# controller.net
KiCad netlist of a schematic drawn in EAGLE
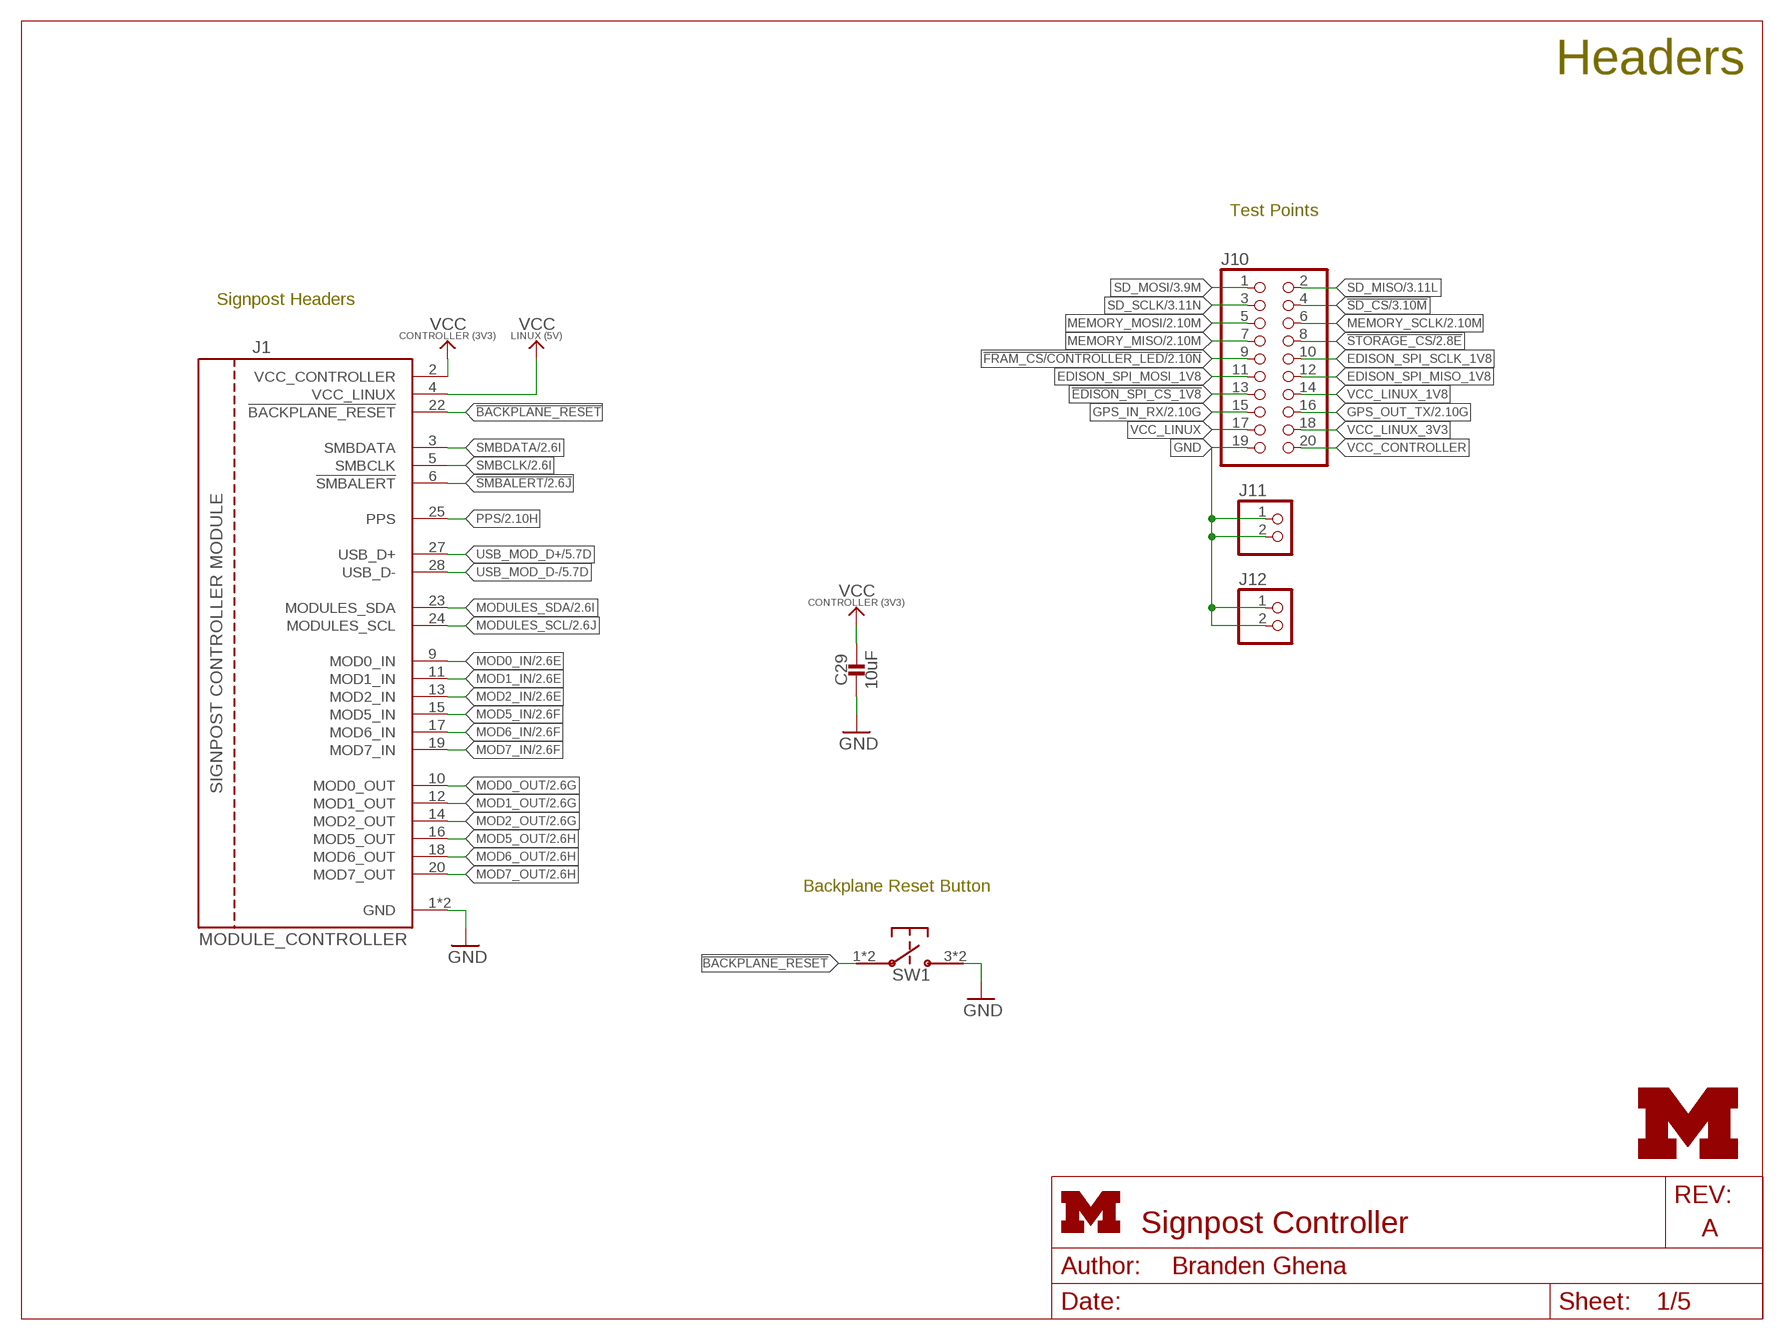
[diagram p0: schematic, sheet 1]
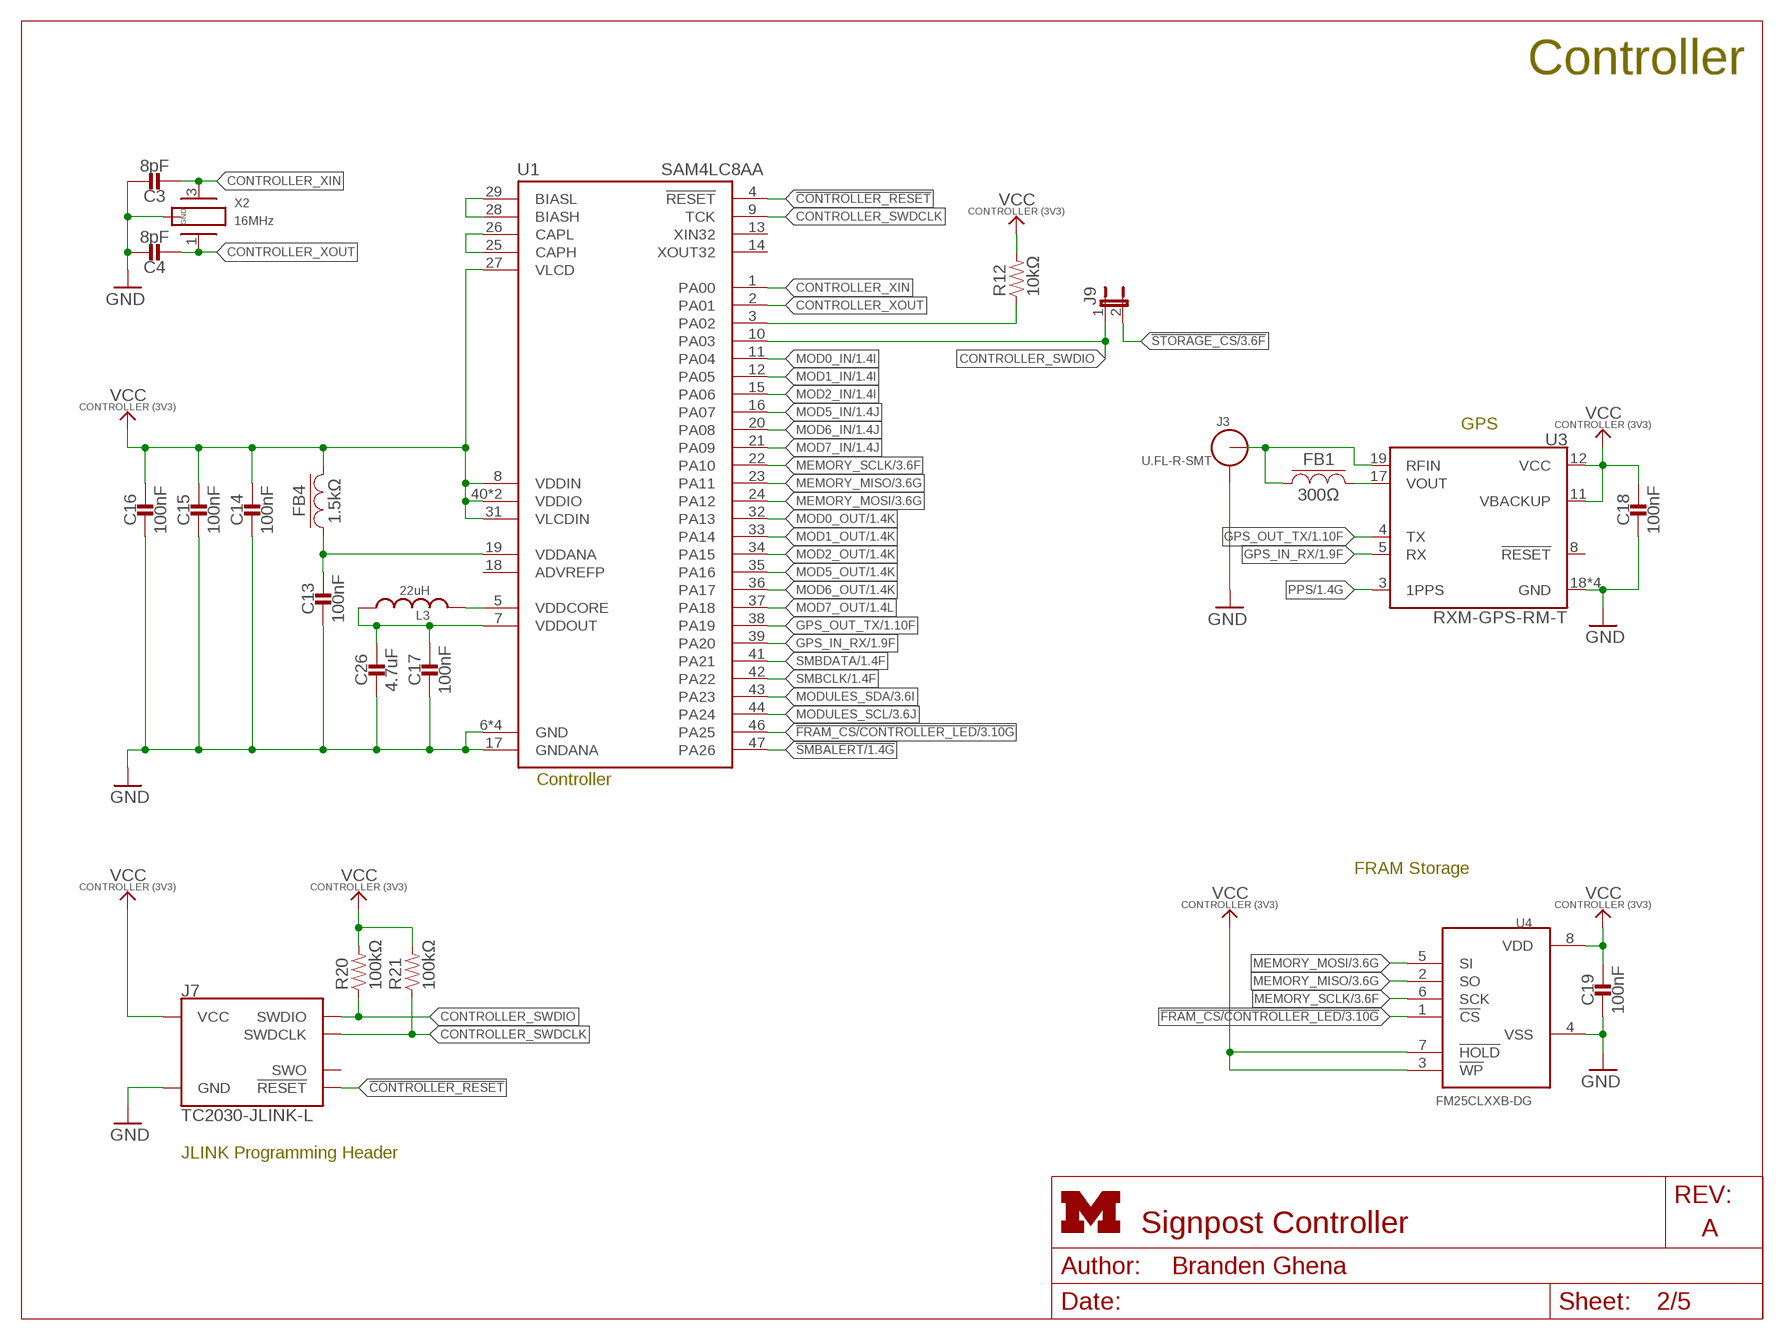
[diagram p1: schematic, sheet 2]
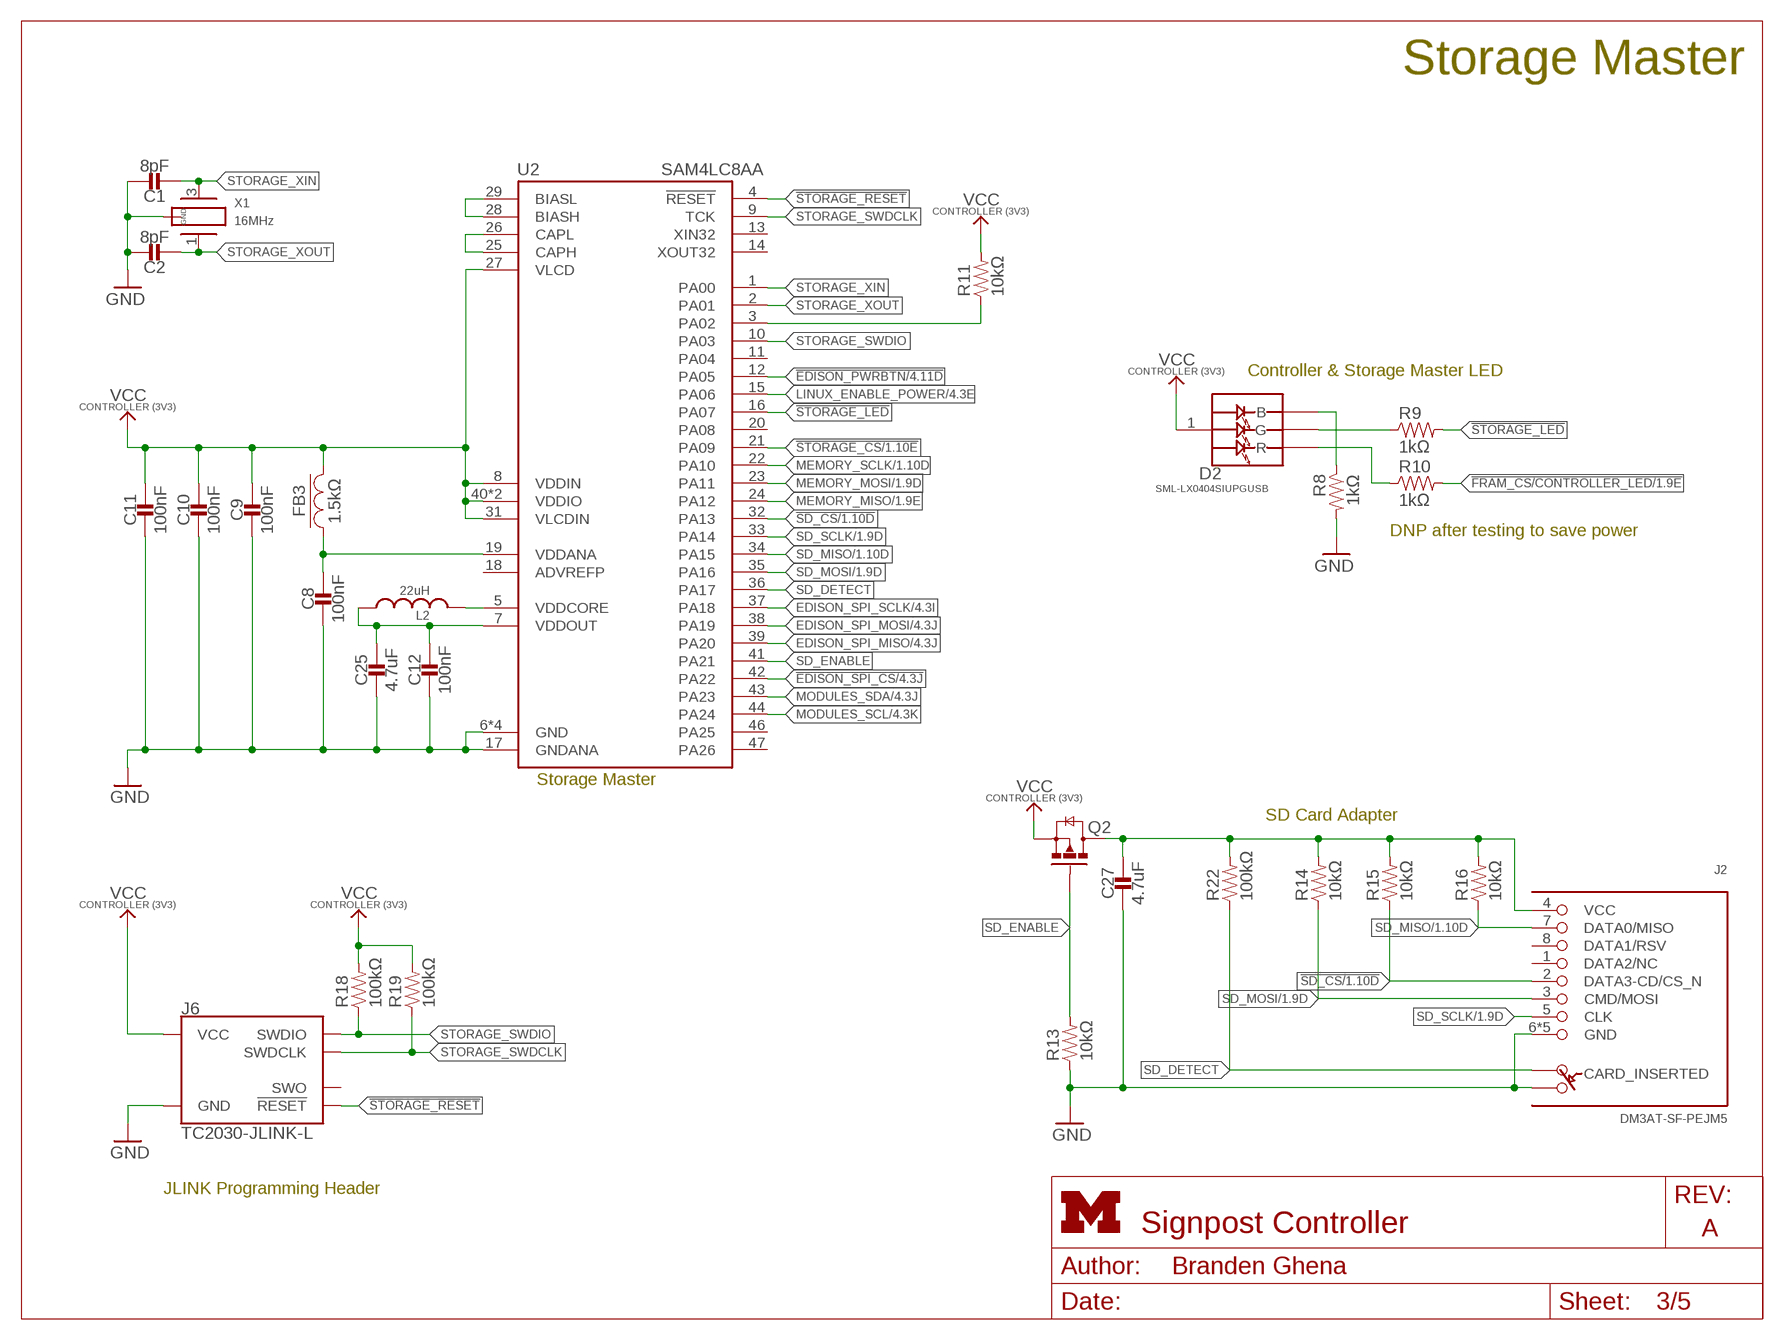
[diagram p2: schematic, sheet 3]
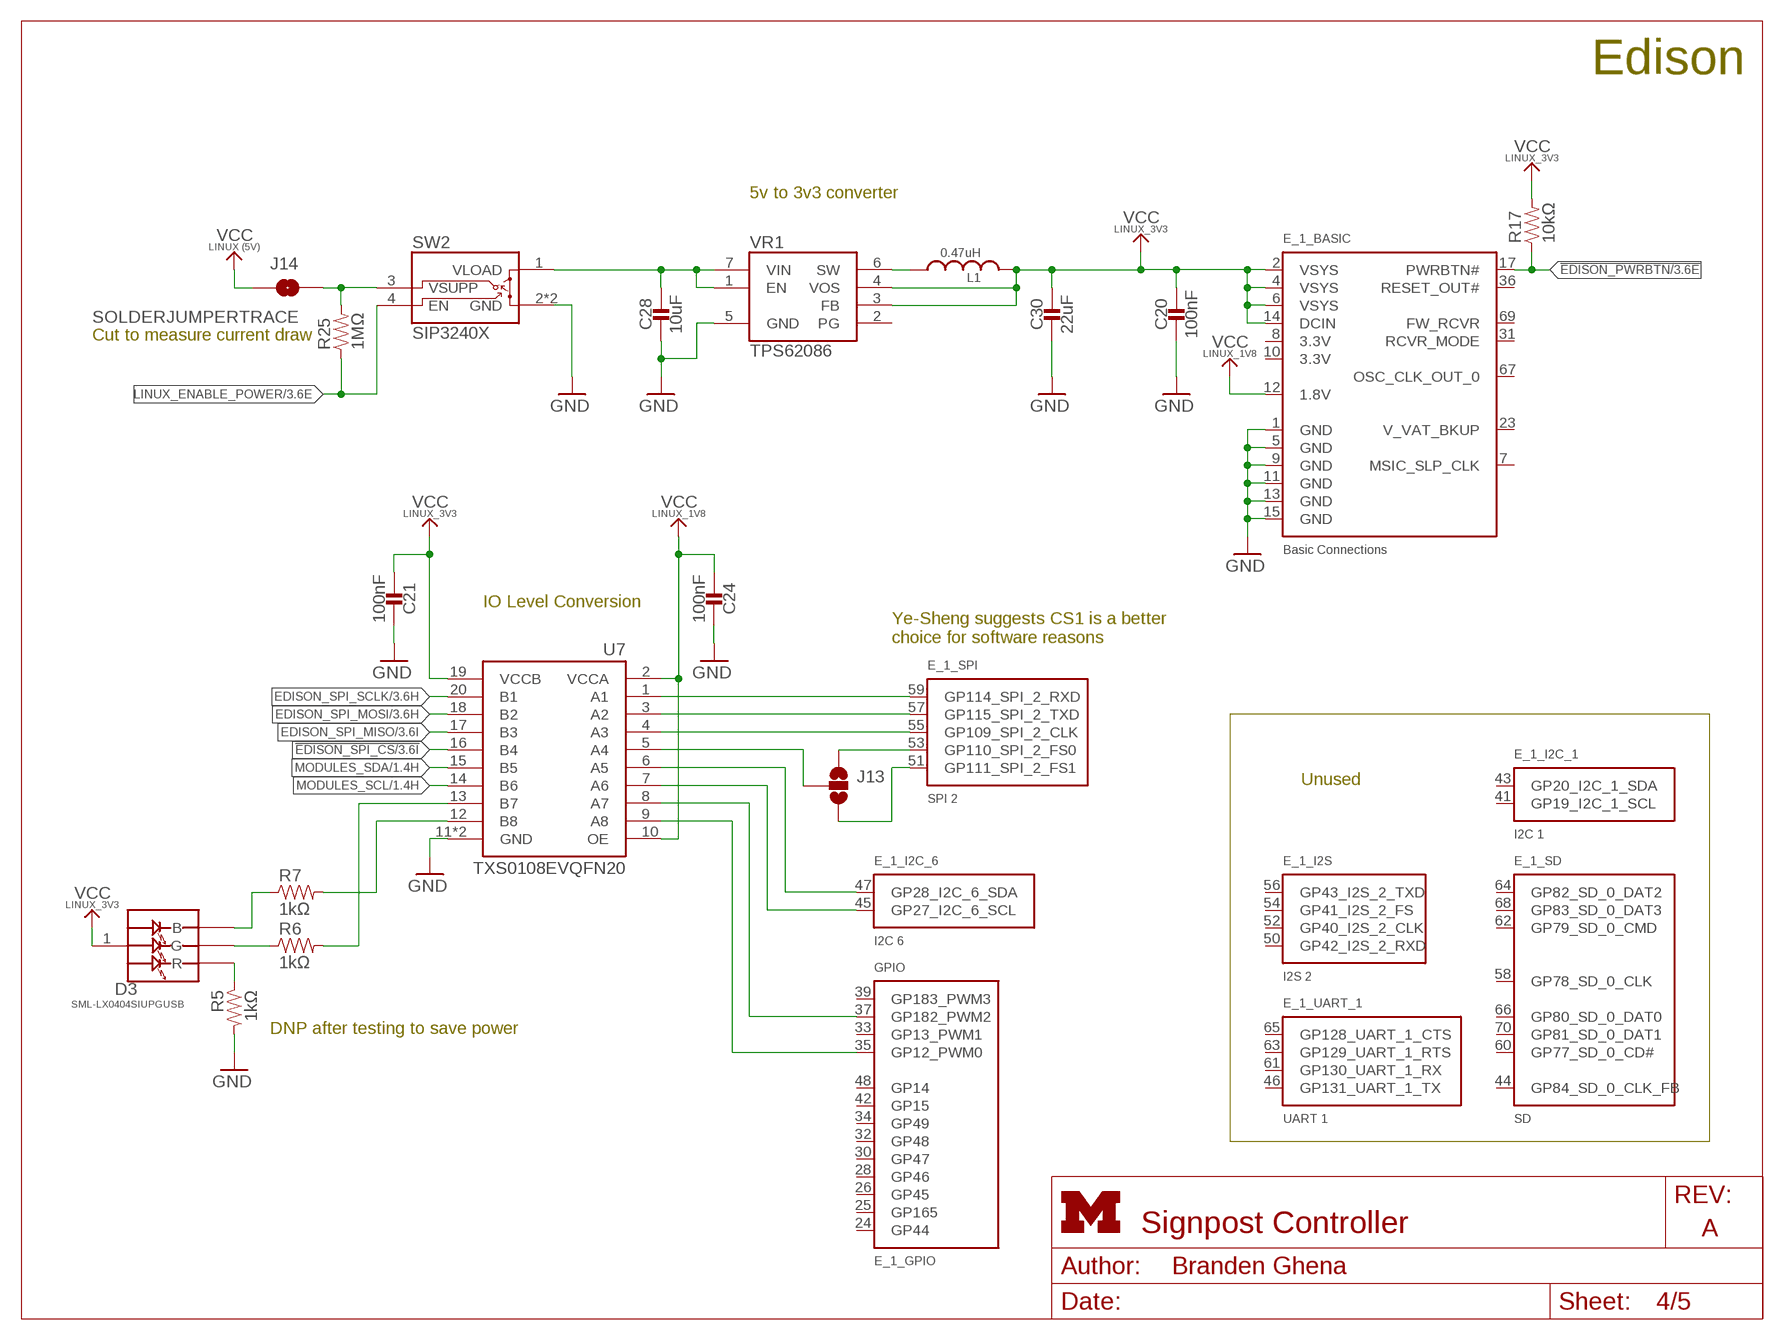
[diagram p3: schematic, sheet 4]
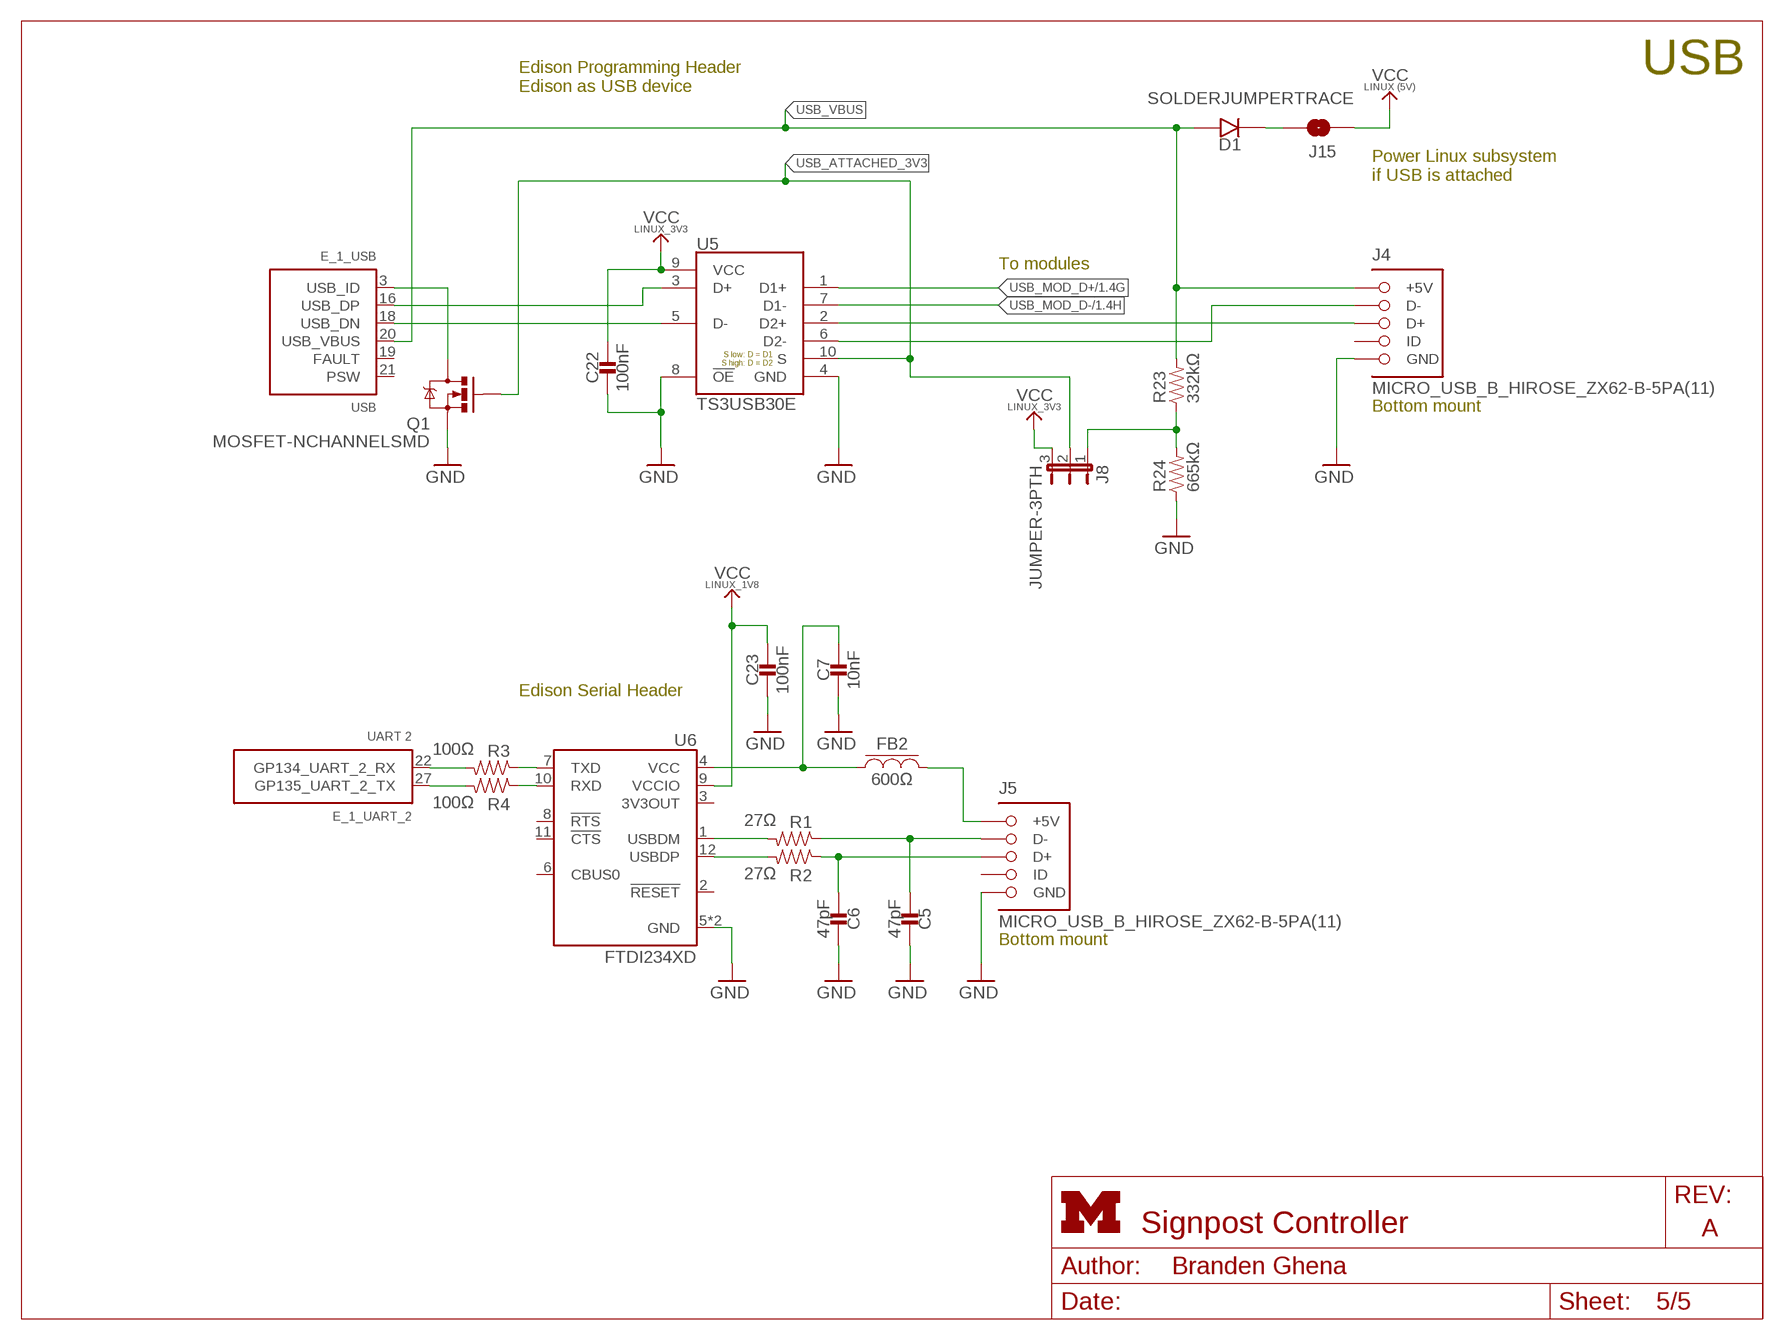
[diagram p4: schematic, sheet 5]

(export (version "E")
  (design (tool "Eeschema 10.0.6"))
  (components
    (comp (ref "C5")
      (value "47pF")
      (footprint "eagle-import:0402_CAP")
      (libsource (lib "eagle-import") (part "CAPACITOR0402_CAP"))
    )
    (comp (ref "C6")
      (value "47pF")
      (footprint "eagle-import:0402_CAP")
      (libsource (lib "eagle-import") (part "CAPACITOR0402_CAP"))
    )
    (comp (ref "C7")
      (value "10nF")
      (footprint "eagle-import:0402_CAP")
      (libsource (lib "eagle-import") (part "CAPACITOR0402_CAP"))
    )
    (comp (ref "C22")
      (value "100nF")
      (footprint "eagle-import:0402_CAP")
      (libsource (lib "eagle-import") (part "CAPACITOR0402_CAP"))
    )
    (comp (ref "C23")
      (value "100nF")
      (footprint "eagle-import:0402_CAP")
      (libsource (lib "eagle-import") (part "CAPACITOR0402_CAP"))
    )
    (comp (ref "D1")
      (value "DIODE")
      (footprint "eagle-import:0402_DIODE")
      (libsource (lib "eagle-import") (part "DIODE"))
    )
    (comp (ref "E_1")
      (value "EDISON_CONNECTOR_SEGMENTED")
      (footprint "eagle-import:EDISON_DAUGHTER")
      (fields (field (name "AMAZON") "B00PTVSS4A") (field (name "MOUSER") "798-DF40HC3070DS4V51"))
      (libsource (lib "eagle-import") (part "EDISON_CONNECTOR_SEGMENTED"))
    )
    (comp (ref "FB2")
      (value "600Ω")
      (footprint "eagle-import:0805_CAP")
      (libsource (lib "eagle-import") (part "FERRITE_BEAD0805"))
    )
    (comp (ref "J4")
      (value "MICRO_USB_B_HIROSE_ZX62-B-5PA(11)")
      (footprint "eagle-import:USB_MICRO_B-HIROSE-ZX62-B-5PA(11)")
      (libsource (lib "eagle-import") (part "MICRO_USB_B_HIROSE_ZX62-B-5PA(11)"))
    )
    (comp (ref "J5")
      (value "MICRO_USB_B_HIROSE_ZX62-B-5PA(11)")
      (footprint "eagle-import:USB_MICRO_B-HIROSE-ZX62-B-5PA(11)")
      (libsource (lib "eagle-import") (part "MICRO_USB_B_HIROSE_ZX62-B-5PA(11)"))
    )
    (comp (ref "J8")
      (value "JUMPER-3PTH")
      (footprint "eagle-import:1X03")
      (libsource (lib "eagle-import") (part "JUMPER-3PTH"))
    )
    (comp (ref "J15")
      (value "SOLDERJUMPERTRACE")
      (footprint "eagle-import:SJ_2S-TRACE")
      (libsource (lib "eagle-import") (part "SOLDERJUMPERTRACE"))
    )
    (comp (ref "Q1")
      (value "MOSFET-NCHANNELSMD")
      (footprint "eagle-import:SOT23-3")
      (libsource (lib "eagle-import") (part "MOSFET-NCHANNELSMD"))
    )
    (comp (ref "R1")
      (value "27Ω")
      (footprint "eagle-import:0402_RES")
      (libsource (lib "eagle-import") (part "RESISTOR0402_RES"))
    )
    (comp (ref "R2")
      (value "27Ω")
      (footprint "eagle-import:0402_RES")
      (libsource (lib "eagle-import") (part "RESISTOR0402_RES"))
    )
    (comp (ref "R3")
      (value "100Ω")
      (footprint "eagle-import:0402_RES")
      (libsource (lib "eagle-import") (part "RESISTOR0402_RES"))
    )
    (comp (ref "R4")
      (value "100Ω")
      (footprint "eagle-import:0402_RES")
      (libsource (lib "eagle-import") (part "RESISTOR0402_RES"))
    )
    (comp (ref "R23")
      (value "332kΩ")
      (footprint "eagle-import:0402_RES")
      (libsource (lib "eagle-import") (part "RESISTOR0402_RES"))
    )
    (comp (ref "R24")
      (value "665kΩ")
      (footprint "eagle-import:0402_RES")
      (libsource (lib "eagle-import") (part "RESISTOR0402_RES"))
    )
    (comp (ref "U5")
      (value "TS3USB30E")
      (footprint "eagle-import:UQFN-10")
      (libsource (lib "eagle-import") (part "TS3USB30E"))
    )
    (comp (ref "U6")
      (value "FTDI234XD")
      (footprint "eagle-import:DFN-12_3MM")
      (libsource (lib "eagle-import") (part "FTDI234XD"))
    )
    (comp (ref "C29")
      (value "10uF")
      (footprint "eagle-import:0402_CAP")
      (libsource (lib "eagle-import") (part "CAPACITOR0402_CAP"))
    )
    (comp (ref "J1")
      (value "MODULE_CONTROLLER")
      (footprint "eagle-import:MODULE_CONTROLLER")
      (libsource (lib "eagle-import") (part "MODULE_CONTROLLER"))
    )
    (comp (ref "J10")
      (value "PINHD-2X10")
      (footprint "eagle-import:2X10")
      (libsource (lib "eagle-import") (part "PINHD-2X10"))
    )
    (comp (ref "J11")
      (value "PINHD-1X2")
      (footprint "eagle-import:1X02")
      (libsource (lib "eagle-import") (part "PINHD-1X2"))
    )
    (comp (ref "J12")
      (value "PINHD-1X2")
      (footprint "eagle-import:1X02")
      (libsource (lib "eagle-import") (part "PINHD-1X2"))
    )
    (comp (ref "LOGO1")
      (value "UMICH_SOLID_MEDIUM")
      (footprint "eagle-import:UMICH_SOLID_200MIL")
      (libsource (lib "eagle-import") (part "UMICH_SOLID_MEDIUM"))
    )
    (comp (ref "SW1")
      (value "PTS810SJ")
      (footprint "eagle-import:PTS810SJ")
      (libsource (lib "eagle-import") (part "PTS810SJ"))
    )
    (comp (ref "C3")
      (value "8pF")
      (footprint "eagle-import:0402_CAP")
      (libsource (lib "eagle-import") (part "CAPACITOR0402_CAP"))
    )
    (comp (ref "C4")
      (value "8pF")
      (footprint "eagle-import:0402_CAP")
      (libsource (lib "eagle-import") (part "CAPACITOR0402_CAP"))
    )
    (comp (ref "C13")
      (value "100nF")
      (footprint "eagle-import:0402_CAP")
      (libsource (lib "eagle-import") (part "CAPACITOR0402_CAP"))
    )
    (comp (ref "C14")
      (value "100nF")
      (footprint "eagle-import:0402_CAP")
      (libsource (lib "eagle-import") (part "CAPACITOR0402_CAP"))
    )
    (comp (ref "C15")
      (value "100nF")
      (footprint "eagle-import:0402_CAP")
      (libsource (lib "eagle-import") (part "CAPACITOR0402_CAP"))
    )
    (comp (ref "C16")
      (value "100nF")
      (footprint "eagle-import:0402_CAP")
      (libsource (lib "eagle-import") (part "CAPACITOR0402_CAP"))
    )
    (comp (ref "C17")
      (value "100nF")
      (footprint "eagle-import:0402_CAP")
      (libsource (lib "eagle-import") (part "CAPACITOR0402_CAP"))
    )
    (comp (ref "C18")
      (value "100nF")
      (footprint "eagle-import:0402_CAP")
      (libsource (lib "eagle-import") (part "CAPACITOR0402_CAP"))
    )
    (comp (ref "C19")
      (value "100nF")
      (footprint "eagle-import:0402_CAP")
      (libsource (lib "eagle-import") (part "CAPACITOR0402_CAP"))
    )
    (comp (ref "C26")
      (value "4.7uF")
      (footprint "eagle-import:0402_CAP")
      (libsource (lib "eagle-import") (part "CAPACITOR0402_CAP"))
    )
    (comp (ref "FB1")
      (value "300Ω")
      (footprint "eagle-import:0402_CAP")
      (libsource (lib "eagle-import") (part "FERRITE_BEAD0402"))
    )
    (comp (ref "FB4")
      (value "1.5kΩ")
      (footprint "eagle-import:0402_CAP")
      (libsource (lib "eagle-import") (part "FERRITE_BEAD0402"))
    )
    (comp (ref "J3")
      (value "U.FL-R-SMT")
      (footprint "eagle-import:U.FL_SMT")
      (libsource (lib "eagle-import") (part "U.FL-R-SMT"))
    )
    (comp (ref "J7")
      (value "TC2030-JLINK-L")
      (footprint "eagle-import:TC2030-IDC")
      (libsource (lib "eagle-import") (part "TC2030-JLINK-L"))
    )
    (comp (ref "J9")
      (value "JUMPER-2PTH")
      (footprint "eagle-import:1X02")
      (libsource (lib "eagle-import") (part "JUMPER-2PTH"))
    )
    (comp (ref "L3")
      (value "22uH")
      (footprint "eagle-import:1212")
      (libsource (lib "eagle-import") (part "LHQ3NP"))
    )
    (comp (ref "R12")
      (value "10kΩ")
      (footprint "eagle-import:0402_RES")
      (libsource (lib "eagle-import") (part "RESISTOR0402_RES"))
    )
    (comp (ref "R20")
      (value "100kΩ")
      (footprint "eagle-import:0402_RES")
      (libsource (lib "eagle-import") (part "RESISTOR0402_RES"))
    )
    (comp (ref "R21")
      (value "100kΩ")
      (footprint "eagle-import:0402_RES")
      (libsource (lib "eagle-import") (part "RESISTOR0402_RES"))
    )
    (comp (ref "U1")
      (value "SAM4LC8AA")
      (footprint "eagle-import:QFN-48-7MM")
      (libsource (lib "eagle-import") (part "SAM4LC8AA"))
    )
    (comp (ref "U3")
      (value "RXM-GPS-RM-T")
      (footprint "eagle-import:RXM-GPS-RM-T")
      (libsource (lib "eagle-import") (part "RXM-GPS-RM-T"))
    )
    (comp (ref "U4")
      (value "FM25CLXXB-DG")
      (footprint "eagle-import:TDFN-8")
      (libsource (lib "eagle-import") (part "FM25CLXXB-DG"))
    )
    (comp (ref "X2")
      (value "16MHz")
      (footprint "eagle-import:FHXXX")
      (libsource (lib "eagle-import") (part "FH1600015"))
    )
    (comp (ref "C20")
      (value "100nF")
      (footprint "eagle-import:0402_CAP")
      (libsource (lib "eagle-import") (part "CAPACITOR0402_CAP"))
    )
    (comp (ref "C21")
      (value "100nF")
      (footprint "eagle-import:0402_CAP")
      (libsource (lib "eagle-import") (part "CAPACITOR0402_CAP"))
    )
    (comp (ref "C24")
      (value "100nF")
      (footprint "eagle-import:0402_CAP")
      (libsource (lib "eagle-import") (part "CAPACITOR0402_CAP"))
    )
    (comp (ref "C28")
      (value "10uF")
      (footprint "eagle-import:0805_CAP")
      (libsource (lib "eagle-import") (part "CAPACITOR0805_CAP"))
    )
    (comp (ref "C30")
      (value "22uF")
      (footprint "eagle-import:0805_CAP")
      (libsource (lib "eagle-import") (part "CAPACITOR0805_CAP"))
    )
    (comp (ref "D3")
      (value "SML-LX0404SIUPGUSB")
      (footprint "eagle-import:1MM_SQ_4PAD")
      (libsource (lib "eagle-import") (part "SML-LX0404SIUPGUSB"))
    )
    (comp (ref "J13")
      (value "SOLDERJUMPER_2WAYPASTE2&3")
      (footprint "eagle-import:SJ_3_PASTE2&3")
      (libsource (lib "eagle-import") (part "SOLDERJUMPER_2WAYPASTE2&3"))
    )
    (comp (ref "J14")
      (value "SOLDERJUMPERTRACE")
      (footprint "eagle-import:SJ_2S-TRACE")
      (libsource (lib "eagle-import") (part "SOLDERJUMPERTRACE"))
    )
    (comp (ref "L1")
      (value "0.47uH")
      (footprint "eagle-import:DFE322512C")
      (libsource (lib "eagle-import") (part "INDUCTORDFE322512C"))
    )
    (comp (ref "R5")
      (value "1kΩ")
      (footprint "eagle-import:0402_RES")
      (libsource (lib "eagle-import") (part "RESISTOR0402_RES"))
    )
    (comp (ref "R6")
      (value "1kΩ")
      (footprint "eagle-import:0402_RES")
      (libsource (lib "eagle-import") (part "RESISTOR0402_RES"))
    )
    (comp (ref "R7")
      (value "1kΩ")
      (footprint "eagle-import:0402_RES")
      (libsource (lib "eagle-import") (part "RESISTOR0402_RES"))
    )
    (comp (ref "R17")
      (value "10kΩ")
      (footprint "eagle-import:0402_RES")
      (libsource (lib "eagle-import") (part "RESISTOR0402_RES"))
    )
    (comp (ref "R25")
      (value "1MΩ")
      (footprint "eagle-import:0402_RES")
      (libsource (lib "eagle-import") (part "RESISTOR0402_RES"))
    )
    (comp (ref "SW2")
      (value "SIP3240X")
      (footprint "eagle-import:TDFN4")
      (libsource (lib "eagle-import") (part "SIP3240X"))
    )
    (comp (ref "U7")
      (value "TXS0108EVQFN20")
      (footprint "eagle-import:R-PVQFN-N20")
      (libsource (lib "eagle-import") (part "TXS0108EVQFN20"))
    )
    (comp (ref "VR1")
      (value "TPS62086")
      (footprint "eagle-import:RLT0007A")
      (libsource (lib "eagle-import") (part "TPS62086"))
    )
    (comp (ref "C1")
      (value "8pF")
      (footprint "eagle-import:0402_CAP")
      (libsource (lib "eagle-import") (part "CAPACITOR0402_CAP"))
    )
    (comp (ref "C2")
      (value "8pF")
      (footprint "eagle-import:0402_CAP")
      (libsource (lib "eagle-import") (part "CAPACITOR0402_CAP"))
    )
    (comp (ref "C8")
      (value "100nF")
      (footprint "eagle-import:0402_CAP")
      (libsource (lib "eagle-import") (part "CAPACITOR0402_CAP"))
    )
    (comp (ref "C9")
      (value "100nF")
      (footprint "eagle-import:0402_CAP")
      (libsource (lib "eagle-import") (part "CAPACITOR0402_CAP"))
    )
    (comp (ref "C10")
      (value "100nF")
      (footprint "eagle-import:0402_CAP")
      (libsource (lib "eagle-import") (part "CAPACITOR0402_CAP"))
    )
    (comp (ref "C11")
      (value "100nF")
      (footprint "eagle-import:0402_CAP")
      (libsource (lib "eagle-import") (part "CAPACITOR0402_CAP"))
    )
    (comp (ref "C12")
      (value "100nF")
      (footprint "eagle-import:0402_CAP")
      (libsource (lib "eagle-import") (part "CAPACITOR0402_CAP"))
    )
    (comp (ref "C25")
      (value "4.7uF")
      (footprint "eagle-import:0402_CAP")
      (libsource (lib "eagle-import") (part "CAPACITOR0402_CAP"))
    )
    (comp (ref "C27")
      (value "4.7uF")
      (footprint "eagle-import:0402_CAP")
      (libsource (lib "eagle-import") (part "CAPACITOR0402_CAP"))
    )
    (comp (ref "D2")
      (value "SML-LX0404SIUPGUSB")
      (footprint "eagle-import:1MM_SQ_4PAD")
      (libsource (lib "eagle-import") (part "SML-LX0404SIUPGUSB"))
    )
    (comp (ref "FB3")
      (value "1.5kΩ")
      (footprint "eagle-import:0402_CAP")
      (libsource (lib "eagle-import") (part "FERRITE_BEAD0402"))
    )
    (comp (ref "J2")
      (value "DM3AT-SF-PEJM5")
      (footprint "eagle-import:DM3AT-SF-PEJM5")
      (libsource (lib "eagle-import") (part "DM3AT-SF-PEJM5"))
    )
    (comp (ref "J6")
      (value "TC2030-JLINK-L")
      (footprint "eagle-import:TC2030-IDC")
      (libsource (lib "eagle-import") (part "TC2030-JLINK-L"))
    )
    (comp (ref "L2")
      (value "22uH")
      (footprint "eagle-import:1212")
      (libsource (lib "eagle-import") (part "LHQ3NP"))
    )
    (comp (ref "Q2")
      (value "NX3008PBK")
      (footprint "eagle-import:SOT23-3")
      (libsource (lib "eagle-import") (part "NX3008PBK"))
    )
    (comp (ref "R8")
      (value "1kΩ")
      (footprint "eagle-import:0402_RES")
      (libsource (lib "eagle-import") (part "RESISTOR0402_RES"))
    )
    (comp (ref "R9")
      (value "1kΩ")
      (footprint "eagle-import:0402_RES")
      (libsource (lib "eagle-import") (part "RESISTOR0402_RES"))
    )
    (comp (ref "R10")
      (value "1kΩ")
      (footprint "eagle-import:0402_RES")
      (libsource (lib "eagle-import") (part "RESISTOR0402_RES"))
    )
    (comp (ref "R11")
      (value "10kΩ")
      (footprint "eagle-import:0402_RES")
      (libsource (lib "eagle-import") (part "RESISTOR0402_RES"))
    )
    (comp (ref "R13")
      (value "10kΩ")
      (footprint "eagle-import:0402_RES")
      (libsource (lib "eagle-import") (part "RESISTOR0402_RES"))
    )
    (comp (ref "R14")
      (value "10kΩ")
      (footprint "eagle-import:0402_RES")
      (libsource (lib "eagle-import") (part "RESISTOR0402_RES"))
    )
    (comp (ref "R15")
      (value "10kΩ")
      (footprint "eagle-import:0402_RES")
      (libsource (lib "eagle-import") (part "RESISTOR0402_RES"))
    )
    (comp (ref "R16")
      (value "10kΩ")
      (footprint "eagle-import:0402_RES")
      (libsource (lib "eagle-import") (part "RESISTOR0402_RES"))
    )
    (comp (ref "R18")
      (value "100kΩ")
      (footprint "eagle-import:0402_RES")
      (libsource (lib "eagle-import") (part "RESISTOR0402_RES"))
    )
    (comp (ref "R19")
      (value "100kΩ")
      (footprint "eagle-import:0402_RES")
      (libsource (lib "eagle-import") (part "RESISTOR0402_RES"))
    )
    (comp (ref "R22")
      (value "100kΩ")
      (footprint "eagle-import:0402_RES")
      (libsource (lib "eagle-import") (part "RESISTOR0402_RES"))
    )
    (comp (ref "U2")
      (value "SAM4LC8AA")
      (footprint "eagle-import:QFN-48-7MM")
      (libsource (lib "eagle-import") (part "SAM4LC8AA"))
    )
    (comp (ref "X1")
      (value "16MHz")
      (footprint "eagle-import:FHXXX")
      (libsource (lib "eagle-import") (part "FH1600015"))
    )
  )
  (nets
    (net (code "1") (name "CONTROLLER_SWDCLK") (class "Default")
      (node (ref "J7") (pin "4") (pinfunction "SWDCLK_4") (pintype "bidirectional"))
      (node (ref "R21") (pin "1") (pinfunction "1_1") (pintype "passive"))
      (node (ref "U1") (pin "9") (pinfunction "TCK_9") (pintype "bidirectional"))
    )
    (net (code "2") (name "CONTROLLER_SWDIO") (class "Default")
      (node (ref "J7") (pin "2") (pinfunction "SWDIO_2") (pintype "bidirectional"))
      (node (ref "J9") (pin "1") (pinfunction "1_1") (pintype "passive"))
      (node (ref "R20") (pin "1") (pinfunction "1_1") (pintype "passive"))
      (node (ref "U1") (pin "10") (pinfunction "PA03_10") (pintype "bidirectional"))
    )
    (net (code "3") (name "CONTROLLER_XIN") (class "Default")
      (node (ref "C3") (pin "1") (pinfunction "1_1") (pintype "bidirectional"))
      (node (ref "U1") (pin "1") (pinfunction "PA00_1") (pintype "bidirectional"))
      (node (ref "X2") (pin "3") (pinfunction "2_3") (pintype "bidirectional"))
    )
    (net (code "4") (name "CONTROLLER_XOUT") (class "Default")
      (node (ref "C4") (pin "1") (pinfunction "1_1") (pintype "bidirectional"))
      (node (ref "U1") (pin "2") (pinfunction "PA01_2") (pintype "bidirectional"))
      (node (ref "X2") (pin "1") (pinfunction "1_1") (pintype "bidirectional"))
    )
    (net (code "5") (name "EDISON_SPI_MISO") (class "Default")
      (node (ref "U2") (pin "39") (pinfunction "PA20_39") (pintype "bidirectional"))
      (node (ref "U7") (pin "17") (pinfunction "B3_17") (pintype "bidirectional"))
    )
    (net (code "6") (name "EDISON_SPI_MISO_1V8") (class "Default")
      (node (ref "E_1") (pin "55") (pinfunction "GP109_SPI_2_CLK_55") (pintype "bidirectional"))
      (node (ref "J10") (pin "12") (pinfunction "12_12") (pintype "passive"))
      (node (ref "U7") (pin "4") (pinfunction "A3_4") (pintype "bidirectional"))
    )
    (net (code "7") (name "EDISON_SPI_MOSI") (class "Default")
      (node (ref "U2") (pin "38") (pinfunction "PA19_38") (pintype "bidirectional"))
      (node (ref "U7") (pin "18") (pinfunction "B2_18") (pintype "bidirectional"))
    )
    (net (code "8") (name "EDISON_SPI_MOSI_1V8") (class "Default")
      (node (ref "E_1") (pin "57") (pinfunction "GP115_SPI_2_TXD_57") (pintype "bidirectional"))
      (node (ref "J10") (pin "11") (pinfunction "11_11") (pintype "passive"))
      (node (ref "U7") (pin "3") (pinfunction "A2_3") (pintype "bidirectional"))
    )
    (net (code "9") (name "EDISON_SPI_SCLK") (class "Default")
      (node (ref "U2") (pin "37") (pinfunction "PA18_37") (pintype "bidirectional"))
      (node (ref "U7") (pin "20") (pinfunction "B1_20") (pintype "bidirectional"))
    )
    (net (code "10") (name "EDISON_SPI_SCLK_1V8") (class "Default")
      (node (ref "E_1") (pin "59") (pinfunction "GP114_SPI_2_RXD_59") (pintype "bidirectional"))
      (node (ref "J10") (pin "10") (pinfunction "10_10") (pintype "passive"))
      (node (ref "U7") (pin "1") (pinfunction "A1_1") (pintype "bidirectional"))
    )
    (net (code "11") (name "GND") (class "Default")
      (node (ref "C1") (pin "2") (pinfunction "2_2") (pintype "bidirectional"))
      (node (ref "C10") (pin "2") (pinfunction "2_2") (pintype "bidirectional"))
      (node (ref "C11") (pin "2") (pinfunction "2_2") (pintype "bidirectional"))
      (node (ref "C12") (pin "2") (pinfunction "2_2") (pintype "bidirectional"))
      (node (ref "C13") (pin "2") (pinfunction "2_2") (pintype "bidirectional"))
      (node (ref "C14") (pin "2") (pinfunction "2_2") (pintype "bidirectional"))
      (node (ref "C15") (pin "2") (pinfunction "2_2") (pintype "bidirectional"))
      (node (ref "C16") (pin "2") (pinfunction "2_2") (pintype "bidirectional"))
      (node (ref "C17") (pin "2") (pinfunction "2_2") (pintype "bidirectional"))
      (node (ref "C18") (pin "2") (pinfunction "2_2") (pintype "bidirectional"))
      (node (ref "C19") (pin "2") (pinfunction "2_2") (pintype "bidirectional"))
      (node (ref "C2") (pin "2") (pinfunction "2_2") (pintype "bidirectional"))
      (node (ref "C20") (pin "2") (pinfunction "2_2") (pintype "bidirectional"))
      (node (ref "C21") (pin "1") (pinfunction "1_1") (pintype "bidirectional"))
      (node (ref "C22") (pin "2") (pinfunction "2_2") (pintype "bidirectional"))
      (node (ref "C23") (pin "2") (pinfunction "2_2") (pintype "bidirectional"))
      (node (ref "C24") (pin "1") (pinfunction "1_1") (pintype "bidirectional"))
      (node (ref "C25") (pin "2") (pinfunction "2_2") (pintype "bidirectional"))
      (node (ref "C26") (pin "2") (pinfunction "2_2") (pintype "bidirectional"))
      (node (ref "C27") (pin "2") (pinfunction "2_2") (pintype "bidirectional"))
      (node (ref "C28") (pin "P$2") (pinfunction "2_P$2") (pintype "bidirectional"))
      (node (ref "C29") (pin "2") (pinfunction "2_2") (pintype "bidirectional"))
      (node (ref "C3") (pin "2") (pinfunction "2_2") (pintype "bidirectional"))
      (node (ref "C30") (pin "P$2") (pinfunction "2_P$2") (pintype "bidirectional"))
      (node (ref "C4") (pin "2") (pinfunction "2_2") (pintype "bidirectional"))
      (node (ref "C5") (pin "2") (pinfunction "2_2") (pintype "bidirectional"))
      (node (ref "C6") (pin "2") (pinfunction "2_2") (pintype "bidirectional"))
      (node (ref "C7") (pin "2") (pinfunction "2_2") (pintype "bidirectional"))
      (node (ref "C8") (pin "2") (pinfunction "2_2") (pintype "bidirectional"))
      (node (ref "C9") (pin "2") (pinfunction "2_2") (pintype "bidirectional"))
      (node (ref "E_1") (pin "1") (pinfunction "GND_1") (pintype "bidirectional"))
      (node (ref "E_1") (pin "11") (pinfunction "GND_11") (pintype "bidirectional"))
      (node (ref "E_1") (pin "13") (pinfunction "GND_13") (pintype "bidirectional"))
      (node (ref "E_1") (pin "15") (pinfunction "GND_15") (pintype "bidirectional"))
      (node (ref "E_1") (pin "5") (pinfunction "GND_5") (pintype "bidirectional"))
      (node (ref "E_1") (pin "9") (pinfunction "GND_9") (pintype "bidirectional"))
      (node (ref "J1") (pin "1") (pinfunction "GND_1") (pintype "bidirectional"))
      (node (ref "J1") (pin "21") (pinfunction "GND_21") (pintype "bidirectional"))
      (node (ref "J10") (pin "19") (pinfunction "19_19") (pintype "passive"))
      (node (ref "J11") (pin "1") (pinfunction "1_1") (pintype "passive"))
      (node (ref "J11") (pin "2") (pinfunction "2_2") (pintype "passive"))
      (node (ref "J12") (pin "1") (pinfunction "1_1") (pintype "passive"))
      (node (ref "J12") (pin "2") (pinfunction "2_2") (pintype "passive"))
      (node (ref "J2") (pin "6") (pinfunction "GND_6") (pintype "bidirectional"))
      (node (ref "J2") (pin "B") (pinfunction "B_B") (pintype "bidirectional"))
      (node (ref "J2") (pin "MOUNT0") (pinfunction "GND_MOUNT0") (pintype "bidirectional"))
      (node (ref "J2") (pin "MOUNT1") (pinfunction "GND_MOUNT1") (pintype "bidirectional"))
      (node (ref "J2") (pin "MOUNT2") (pinfunction "GND_MOUNT2") (pintype "bidirectional"))
      (node (ref "J2") (pin "MOUNT3") (pinfunction "GND_MOUNT3") (pintype "bidirectional"))
      (node (ref "J3") (pin "GND1") (pinfunction "P$2_GND1") (pintype "bidirectional"))
      (node (ref "J3") (pin "GND2") (pinfunction "P$2_GND2") (pintype "bidirectional"))
      (node (ref "J4") (pin "5") (pinfunction "GND_5") (pintype "bidirectional"))
      (node (ref "J5") (pin "5") (pinfunction "GND_5") (pintype "bidirectional"))
      (node (ref "J6") (pin "5") (pinfunction "GND_5") (pintype "bidirectional"))
      (node (ref "J7") (pin "5") (pinfunction "GND_5") (pintype "bidirectional"))
      (node (ref "Q1") (pin "2") (pinfunction "S_2") (pintype "passive"))
      (node (ref "R13") (pin "1") (pinfunction "1_1") (pintype "passive"))
      (node (ref "R24") (pin "1") (pinfunction "1_1") (pintype "passive"))
      (node (ref "R5") (pin "2") (pinfunction "2_2") (pintype "passive"))
      (node (ref "R8") (pin "2") (pinfunction "2_2") (pintype "passive"))
      (node (ref "SW1") (pin "3") (pinfunction "P$2_3") (pintype "passive"))
      (node (ref "SW1") (pin "4") (pinfunction "P$2_4") (pintype "passive"))
      (node (ref "SW2") (pin "2") (pinfunction "GND_2") (pintype "bidirectional"))
      (node (ref "SW2") (pin "PAD") (pinfunction "GND_PAD") (pintype "bidirectional"))
      (node (ref "U1") (pin "17") (pinfunction "GNDANA_17") (pintype "power_in"))
      (node (ref "U1") (pin "30") (pinfunction "GND_30") (pintype "power_in"))
      (node (ref "U1") (pin "48") (pinfunction "GND_48") (pintype "power_in"))
      (node (ref "U1") (pin "6") (pinfunction "GND_6") (pintype "power_in"))
      (node (ref "U1") (pin "THERMAL") (pinfunction "GND_THERMAL") (pintype "power_in"))
      (node (ref "U2") (pin "17") (pinfunction "GNDANA_17") (pintype "power_in"))
      (node (ref "U2") (pin "30") (pinfunction "GND_30") (pintype "power_in"))
      (node (ref "U2") (pin "48") (pinfunction "GND_48") (pintype "power_in"))
      (node (ref "U2") (pin "6") (pinfunction "GND_6") (pintype "power_in"))
      (node (ref "U2") (pin "THERMAL") (pinfunction "GND_THERMAL") (pintype "power_in"))
      (node (ref "U3") (pin "18") (pinfunction "GND_18") (pintype "bidirectional"))
      (node (ref "U3") (pin "20") (pinfunction "GND_20") (pintype "bidirectional"))
      (node (ref "U3") (pin "21") (pinfunction "GND_21") (pintype "bidirectional"))
      (node (ref "U3") (pin "22") (pinfunction "GND_22") (pintype "bidirectional"))
      (node (ref "U4") (pin "4") (pinfunction "VSS_4") (pintype "bidirectional"))
      (node (ref "U5") (pin "4") (pinfunction "GND_4") (pintype "bidirectional"))
      (node (ref "U5") (pin "8") (pinfunction "~{OE}_8") (pintype "bidirectional"))
      (node (ref "U6") (pin "13") (pinfunction "GND_13") (pintype "bidirectional"))
      (node (ref "U6") (pin "5") (pinfunction "GND_5") (pintype "bidirectional"))
      (node (ref "U7") (pin "11") (pinfunction "GND_11") (pintype "bidirectional"))
      (node (ref "U7") (pin "THERMAL") (pinfunction "GND_THERMAL") (pintype "bidirectional"))
      (node (ref "VR1") (pin "5") (pinfunction "GND_5") (pintype "bidirectional"))
      (node (ref "X1") (pin "2") (pinfunction "GND_2") (pintype "bidirectional"))
      (node (ref "X1") (pin "4") (pinfunction "GND_4") (pintype "bidirectional"))
      (node (ref "X2") (pin "2") (pinfunction "GND_2") (pintype "bidirectional"))
      (node (ref "X2") (pin "4") (pinfunction "GND_4") (pintype "bidirectional"))
    )
    (net (code "12") (name "GPS_IN_RX") (class "Default")
      (node (ref "J10") (pin "15") (pinfunction "15_15") (pintype "passive"))
      (node (ref "U1") (pin "39") (pinfunction "PA20_39") (pintype "bidirectional"))
      (node (ref "U3") (pin "5") (pinfunction "RX_5") (pintype "bidirectional"))
    )
    (net (code "13") (name "GPS_OUT_TX") (class "Default")
      (node (ref "J10") (pin "16") (pinfunction "16_16") (pintype "passive"))
      (node (ref "U1") (pin "38") (pinfunction "PA19_38") (pintype "bidirectional"))
      (node (ref "U3") (pin "4") (pinfunction "TX_4") (pintype "bidirectional"))
    )
    (net (code "14") (name "LINUX_ENABLE_POWER") (class "Default")
      (node (ref "R25") (pin "1") (pinfunction "1_1") (pintype "passive"))
      (node (ref "SW2") (pin "4") (pinfunction "EN_4") (pintype "bidirectional"))
      (node (ref "U2") (pin "15") (pinfunction "PA06_15") (pintype "bidirectional"))
    )
    (net (code "15") (name "MEMORY_MISO") (class "Default")
      (node (ref "J10") (pin "7") (pinfunction "7_7") (pintype "passive"))
      (node (ref "U1") (pin "23") (pinfunction "PA11_23") (pintype "bidirectional"))
      (node (ref "U2") (pin "24") (pinfunction "PA12_24") (pintype "bidirectional"))
      (node (ref "U4") (pin "2") (pinfunction "SO_2") (pintype "bidirectional"))
    )
    (net (code "16") (name "MEMORY_MOSI") (class "Default")
      (node (ref "J10") (pin "5") (pinfunction "5_5") (pintype "passive"))
      (node (ref "U1") (pin "24") (pinfunction "PA12_24") (pintype "bidirectional"))
      (node (ref "U2") (pin "23") (pinfunction "PA11_23") (pintype "bidirectional"))
      (node (ref "U4") (pin "5") (pinfunction "SI_5") (pintype "bidirectional"))
    )
    (net (code "17") (name "MEMORY_SCLK") (class "Default")
      (node (ref "J10") (pin "6") (pinfunction "6_6") (pintype "passive"))
      (node (ref "U1") (pin "22") (pinfunction "PA10_22") (pintype "bidirectional"))
      (node (ref "U2") (pin "22") (pinfunction "PA10_22") (pintype "bidirectional"))
      (node (ref "U4") (pin "6") (pinfunction "SCK_6") (pintype "bidirectional"))
    )
    (net (code "18") (name "MOD0_IN") (class "Default")
      (node (ref "J1") (pin "9") (pinfunction "MOD0_IN_9") (pintype "bidirectional"))
      (node (ref "U1") (pin "11") (pinfunction "PA04_11") (pintype "bidirectional"))
    )
    (net (code "19") (name "MOD0_OUT") (class "Default")
      (node (ref "J1") (pin "10") (pinfunction "MOD0_OUT_10") (pintype "bidirectional"))
      (node (ref "U1") (pin "32") (pinfunction "PA13_32") (pintype "bidirectional"))
    )
    (net (code "20") (name "MOD1_IN") (class "Default")
      (node (ref "J1") (pin "11") (pinfunction "MOD1_IN_11") (pintype "bidirectional"))
      (node (ref "U1") (pin "12") (pinfunction "PA05_12") (pintype "bidirectional"))
    )
    (net (code "21") (name "MOD1_OUT") (class "Default")
      (node (ref "J1") (pin "12") (pinfunction "MOD1_OUT_12") (pintype "bidirectional"))
      (node (ref "U1") (pin "33") (pinfunction "PA14_33") (pintype "bidirectional"))
    )
    (net (code "22") (name "MOD2_IN") (class "Default")
      (node (ref "J1") (pin "13") (pinfunction "MOD2_IN_13") (pintype "bidirectional"))
      (node (ref "U1") (pin "15") (pinfunction "PA06_15") (pintype "bidirectional"))
    )
    (net (code "23") (name "MOD2_OUT") (class "Default")
      (node (ref "J1") (pin "14") (pinfunction "MOD2_OUT_14") (pintype "bidirectional"))
      (node (ref "U1") (pin "34") (pinfunction "PA15_34") (pintype "bidirectional"))
    )
    (net (code "24") (name "MOD5_IN") (class "Default")
      (node (ref "J1") (pin "15") (pinfunction "MOD5_IN_15") (pintype "bidirectional"))
      (node (ref "U1") (pin "16") (pinfunction "PA07_16") (pintype "bidirectional"))
    )
    (net (code "25") (name "MOD5_OUT") (class "Default")
      (node (ref "J1") (pin "16") (pinfunction "MOD5_OUT_16") (pintype "bidirectional"))
      (node (ref "U1") (pin "35") (pinfunction "PA16_35") (pintype "bidirectional"))
    )
    (net (code "26") (name "MOD6_IN") (class "Default")
      (node (ref "J1") (pin "17") (pinfunction "MOD6_IN_17") (pintype "bidirectional"))
      (node (ref "U1") (pin "20") (pinfunction "PA08_20") (pintype "bidirectional"))
    )
    (net (code "27") (name "MOD6_OUT") (class "Default")
      (node (ref "J1") (pin "18") (pinfunction "MOD6_OUT_18") (pintype "bidirectional"))
      (node (ref "U1") (pin "36") (pinfunction "PA17_36") (pintype "bidirectional"))
    )
    (net (code "28") (name "MOD7_IN") (class "Default")
      (node (ref "J1") (pin "19") (pinfunction "MOD7_IN_19") (pintype "bidirectional"))
      (node (ref "U1") (pin "21") (pinfunction "PA09_21") (pintype "bidirectional"))
    )
    (net (code "29") (name "MOD7_OUT") (class "Default")
      (node (ref "J1") (pin "20") (pinfunction "MOD7_OUT_20") (pintype "bidirectional"))
      (node (ref "U1") (pin "37") (pinfunction "PA18_37") (pintype "bidirectional"))
    )
    (net (code "30") (name "MODULES_SCL") (class "Default")
      (node (ref "J1") (pin "24") (pinfunction "MODULES_SCL_24") (pintype "bidirectional"))
      (node (ref "U1") (pin "44") (pinfunction "PA24_44") (pintype "bidirectional"))
      (node (ref "U2") (pin "44") (pinfunction "PA24_44") (pintype "bidirectional"))
      (node (ref "U7") (pin "14") (pinfunction "B6_14") (pintype "bidirectional"))
    )
    (net (code "31") (name "MODULES_SDA") (class "Default")
      (node (ref "J1") (pin "23") (pinfunction "MODULES_SDA_23") (pintype "bidirectional"))
      (node (ref "U1") (pin "43") (pinfunction "PA23_43") (pintype "bidirectional"))
      (node (ref "U2") (pin "43") (pinfunction "PA23_43") (pintype "bidirectional"))
      (node (ref "U7") (pin "15") (pinfunction "B5_15") (pintype "bidirectional"))
    )
    (net (code "32") (name "Net-(C28-1)") (class "Default")
      (node (ref "C28") (pin "P$1") (pinfunction "1_P$1") (pintype "bidirectional"))
      (node (ref "SW2") (pin "1") (pinfunction "VLOAD_1") (pintype "bidirectional"))
      (node (ref "VR1") (pin "1") (pinfunction "EN_1") (pintype "bidirectional"))
      (node (ref "VR1") (pin "7") (pinfunction "VIN_7") (pintype "bidirectional"))
    )
    (net (code "33") (name "Net-(D1-PadCATHODE)") (class "Default")
      (node (ref "D1") (pin "CATHODE") (pinfunction "CATHODE_CATHODE") (pintype "bidirectional"))
      (node (ref "J15") (pin "2") (pinfunction "2_2") (pintype "passive"))
    )
    (net (code "34") (name "Net-(D2-B)") (class "Default")
      (node (ref "D2") (pin "3") (pinfunction "B_3") (pintype "output"))
      (node (ref "R8") (pin "1") (pinfunction "1_1") (pintype "passive"))
    )
    (net (code "35") (name "Net-(D2-G)") (class "Default")
      (node (ref "D2") (pin "4") (pinfunction "G_4") (pintype "output"))
      (node (ref "R9") (pin "1") (pinfunction "1_1") (pintype "passive"))
    )
    (net (code "36") (name "Net-(D2-R)") (class "Default")
      (node (ref "D2") (pin "2") (pinfunction "R_2") (pintype "output"))
      (node (ref "R10") (pin "1") (pinfunction "1_1") (pintype "passive"))
    )
    (net (code "37") (name "Net-(D3-B)") (class "Default")
      (node (ref "D3") (pin "3") (pinfunction "B_3") (pintype "output"))
      (node (ref "R7") (pin "1") (pinfunction "1_1") (pintype "passive"))
    )
    (net (code "38") (name "Net-(D3-G)") (class "Default")
      (node (ref "D3") (pin "4") (pinfunction "G_4") (pintype "output"))
      (node (ref "R6") (pin "1") (pinfunction "1_1") (pintype "passive"))
    )
    (net (code "39") (name "Net-(D3-R)") (class "Default")
      (node (ref "D3") (pin "2") (pinfunction "R_2") (pintype "output"))
      (node (ref "R5") (pin "1") (pinfunction "1_1") (pintype "passive"))
    )
    (net (code "40") (name "Net-(E_1B-GP12_PWM0)") (class "Default")
      (node (ref "E_1") (pin "35") (pinfunction "GP12_PWM0_35") (pintype "bidirectional"))
      (node (ref "U7") (pin "9") (pinfunction "A8_9") (pintype "bidirectional"))
    )
    (net (code "41") (name "Net-(E_1B-GP182_PWM2)") (class "Default")
      (node (ref "E_1") (pin "37") (pinfunction "GP182_PWM2_37") (pintype "bidirectional"))
      (node (ref "U7") (pin "8") (pinfunction "A7_8") (pintype "bidirectional"))
    )
    (net (code "42") (name "Net-(E_1D-GP27_I2C_6_SCL)") (class "Default")
      (node (ref "E_1") (pin "45") (pinfunction "GP27_I2C_6_SCL_45") (pintype "bidirectional"))
      (node (ref "U7") (pin "7") (pinfunction "A6_7") (pintype "bidirectional"))
    )
    (net (code "43") (name "Net-(E_1D-GP28_I2C_6_SDA)") (class "Default")
      (node (ref "E_1") (pin "47") (pinfunction "GP28_I2C_6_SDA_47") (pintype "bidirectional"))
      (node (ref "U7") (pin "6") (pinfunction "A5_6") (pintype "bidirectional"))
    )
    (net (code "44") (name "Net-(E_1G-GP110_SPI_2_FS0)") (class "Default")
      (node (ref "E_1") (pin "53") (pinfunction "GP110_SPI_2_FS0_53") (pintype "bidirectional"))
      (node (ref "J13") (pin "1") (pinfunction "1_1") (pintype "passive"))
    )
    (net (code "45") (name "Net-(E_1G-GP111_SPI_2_FS1)") (class "Default")
      (node (ref "E_1") (pin "51") (pinfunction "GP111_SPI_2_FS1_51") (pintype "bidirectional"))
      (node (ref "J13") (pin "3") (pinfunction "3_3") (pintype "passive"))
    )
    (net (code "46") (name "Net-(E_1I-GP134_UART_2_RX)") (class "Default")
      (node (ref "E_1") (pin "22") (pinfunction "GP134_UART_2_RX_22") (pintype "bidirectional"))
      (node (ref "R3") (pin "2") (pinfunction "2_2") (pintype "passive"))
    )
    (net (code "47") (name "Net-(E_1I-GP135_UART_2_TX)") (class "Default")
      (node (ref "E_1") (pin "27") (pinfunction "GP135_UART_2_TX_27") (pintype "bidirectional"))
      (node (ref "R4") (pin "2") (pinfunction "2_2") (pintype "passive"))
    )
    (net (code "48") (name "Net-(E_1J-USB_DN)") (class "Default")
      (node (ref "E_1") (pin "18") (pinfunction "USB_DN_18") (pintype "bidirectional"))
      (node (ref "U5") (pin "5") (pinfunction "D-_5") (pintype "bidirectional"))
    )
    (net (code "49") (name "Net-(E_1J-USB_DP)") (class "Default")
      (node (ref "E_1") (pin "16") (pinfunction "USB_DP_16") (pintype "bidirectional"))
      (node (ref "U5") (pin "3") (pinfunction "D+_3") (pintype "bidirectional"))
    )
    (net (code "50") (name "Net-(E_1J-USB_ID)") (class "Default")
      (node (ref "E_1") (pin "3") (pinfunction "USB_ID_3") (pintype "bidirectional"))
      (node (ref "Q1") (pin "3") (pinfunction "D_3") (pintype "passive"))
    )
    (net (code "51") (name "Net-(FB1-P$1)") (class "Default")
      (node (ref "FB1") (pin "1") (pinfunction "P$1_1") (pintype "bidirectional"))
      (node (ref "U3") (pin "17") (pinfunction "VOUT_17") (pintype "bidirectional"))
    )
    (net (code "52") (name "Net-(FB1-P$2)") (class "Default")
      (node (ref "FB1") (pin "2") (pinfunction "P$2_2") (pintype "bidirectional"))
      (node (ref "J3") (pin "SIG") (pinfunction "ANT_SIG") (pintype "bidirectional"))
      (node (ref "U3") (pin "19") (pinfunction "RFIN_19") (pintype "bidirectional"))
    )
    (net (code "53") (name "Net-(FB3-P$1)") (class "Default")
      (node (ref "C8") (pin "1") (pinfunction "1_1") (pintype "bidirectional"))
      (node (ref "FB3") (pin "1") (pinfunction "P$1_1") (pintype "bidirectional"))
      (node (ref "U2") (pin "19") (pinfunction "VDDANA_19") (pintype "power_in"))
    )
    (net (code "54") (name "Net-(FB4-P$1)") (class "Default")
      (node (ref "C13") (pin "1") (pinfunction "1_1") (pintype "bidirectional"))
      (node (ref "FB4") (pin "1") (pinfunction "P$1_1") (pintype "bidirectional"))
      (node (ref "U1") (pin "19") (pinfunction "VDDANA_19") (pintype "power_in"))
    )
    (net (code "55") (name "Net-(J2-VCC)") (class "Default")
      (node (ref "C27") (pin "1") (pinfunction "1_1") (pintype "bidirectional"))
      (node (ref "J2") (pin "4") (pinfunction "VCC_4") (pintype "bidirectional"))
      (node (ref "Q2") (pin "3") (pinfunction "D_3") (pintype "passive"))
      (node (ref "R14") (pin "2") (pinfunction "2_2") (pintype "passive"))
      (node (ref "R15") (pin "2") (pinfunction "2_2") (pintype "passive"))
      (node (ref "R16") (pin "2") (pinfunction "2_2") (pintype "passive"))
      (node (ref "R22") (pin "2") (pinfunction "2_2") (pintype "passive"))
    )
    (net (code "56") (name "Net-(J4-D+)") (class "Default")
      (node (ref "J4") (pin "3") (pinfunction "D+_3") (pintype "bidirectional"))
      (node (ref "U5") (pin "2") (pinfunction "D2+_2") (pintype "bidirectional"))
    )
    (net (code "57") (name "Net-(J4-D-)") (class "Default")
      (node (ref "J4") (pin "2") (pinfunction "D-_2") (pintype "bidirectional"))
      (node (ref "U5") (pin "6") (pinfunction "D2-_6") (pintype "bidirectional"))
    )
    (net (code "58") (name "Net-(J5-+5V)") (class "Default")
      (node (ref "FB2") (pin "P$2") (pinfunction "P$2_P$2") (pintype "bidirectional"))
      (node (ref "J5") (pin "1") (pinfunction "+5V_1") (pintype "bidirectional"))
    )
    (net (code "59") (name "Net-(J5-D+)") (class "Default")
      (node (ref "C6") (pin "1") (pinfunction "1_1") (pintype "bidirectional"))
      (node (ref "J5") (pin "3") (pinfunction "D+_3") (pintype "bidirectional"))
      (node (ref "R2") (pin "1") (pinfunction "1_1") (pintype "passive"))
    )
    (net (code "60") (name "Net-(J5-D-)") (class "Default")
      (node (ref "C5") (pin "1") (pinfunction "1_1") (pintype "bidirectional"))
      (node (ref "J5") (pin "2") (pinfunction "D-_2") (pintype "bidirectional"))
      (node (ref "R1") (pin "1") (pinfunction "1_1") (pintype "passive"))
    )
    (net (code "61") (name "Net-(J8-Pad1)") (class "Default")
      (node (ref "J8") (pin "1") (pinfunction "1_1") (pintype "passive"))
      (node (ref "R23") (pin "1") (pinfunction "1_1") (pintype "passive"))
      (node (ref "R24") (pin "2") (pinfunction "2_2") (pintype "passive"))
    )
    (net (code "62") (name "Net-(L1-1)") (class "Default")
      (node (ref "L1") (pin "P$1") (pinfunction "1_P$1") (pintype "bidirectional"))
      (node (ref "VR1") (pin "6") (pinfunction "SW_6") (pintype "bidirectional"))
    )
    (net (code "63") (name "Net-(L2-1)") (class "Default")
      (node (ref "C12") (pin "1") (pinfunction "1_1") (pintype "bidirectional"))
      (node (ref "C25") (pin "1") (pinfunction "1_1") (pintype "bidirectional"))
      (node (ref "L2") (pin "P$1") (pinfunction "1_P$1") (pintype "bidirectional"))
      (node (ref "U2") (pin "7") (pinfunction "VDDOUT_7") (pintype "power_in"))
    )
    (net (code "64") (name "Net-(L2-2)") (class "Default")
      (node (ref "L2") (pin "P$2") (pinfunction "2_P$2") (pintype "bidirectional"))
      (node (ref "U2") (pin "5") (pinfunction "VDDCORE_5") (pintype "power_in"))
    )
    (net (code "65") (name "Net-(L3-1)") (class "Default")
      (node (ref "C17") (pin "1") (pinfunction "1_1") (pintype "bidirectional"))
      (node (ref "C26") (pin "1") (pinfunction "1_1") (pintype "bidirectional"))
      (node (ref "L3") (pin "P$1") (pinfunction "1_P$1") (pintype "bidirectional"))
      (node (ref "U1") (pin "7") (pinfunction "VDDOUT_7") (pintype "power_in"))
    )
    (net (code "66") (name "Net-(L3-2)") (class "Default")
      (node (ref "L3") (pin "P$2") (pinfunction "2_P$2") (pintype "bidirectional"))
      (node (ref "U1") (pin "5") (pinfunction "VDDCORE_5") (pintype "power_in"))
    )
    (net (code "67") (name "Net-(SW2-VSUPP)") (class "Default")
      (node (ref "J14") (pin "2") (pinfunction "2_2") (pintype "passive"))
      (node (ref "R25") (pin "2") (pinfunction "2_2") (pintype "passive"))
      (node (ref "SW2") (pin "3") (pinfunction "VSUPP_3") (pintype "bidirectional"))
    )
    (net (code "68") (name "Net-(U1-BIASH)") (class "Default")
      (node (ref "U1") (pin "28") (pinfunction "BIASH_28") (pintype "bidirectional"))
      (node (ref "U1") (pin "29") (pinfunction "BIASL_29") (pintype "bidirectional"))
    )
    (net (code "69") (name "Net-(U1-CAPH)") (class "Default")
      (node (ref "U1") (pin "25") (pinfunction "CAPH_25") (pintype "bidirectional"))
      (node (ref "U1") (pin "26") (pinfunction "CAPL_26") (pintype "bidirectional"))
    )
    (net (code "70") (name "Net-(U1-PA02)") (class "Default")
      (node (ref "R12") (pin "1") (pinfunction "1_1") (pintype "passive"))
      (node (ref "U1") (pin "3") (pinfunction "PA02_3") (pintype "bidirectional"))
    )
    (net (code "71") (name "Net-(U2-BIASH)") (class "Default")
      (node (ref "U2") (pin "28") (pinfunction "BIASH_28") (pintype "bidirectional"))
      (node (ref "U2") (pin "29") (pinfunction "BIASL_29") (pintype "bidirectional"))
    )
    (net (code "72") (name "Net-(U2-CAPH)") (class "Default")
      (node (ref "U2") (pin "25") (pinfunction "CAPH_25") (pintype "bidirectional"))
      (node (ref "U2") (pin "26") (pinfunction "CAPL_26") (pintype "bidirectional"))
    )
    (net (code "73") (name "Net-(U2-PA02)") (class "Default")
      (node (ref "R11") (pin "1") (pinfunction "1_1") (pintype "passive"))
      (node (ref "U2") (pin "3") (pinfunction "PA02_3") (pintype "bidirectional"))
    )
    (net (code "74") (name "Net-(U6-RXD)") (class "Default")
      (node (ref "R4") (pin "1") (pinfunction "1_1") (pintype "passive"))
      (node (ref "U6") (pin "10") (pinfunction "RXD_10") (pintype "bidirectional"))
    )
    (net (code "75") (name "Net-(U6-TXD)") (class "Default")
      (node (ref "R3") (pin "1") (pinfunction "1_1") (pintype "passive"))
      (node (ref "U6") (pin "7") (pinfunction "TXD_7") (pintype "bidirectional"))
    )
    (net (code "76") (name "Net-(U6-USBDM)") (class "Default")
      (node (ref "R1") (pin "2") (pinfunction "2_2") (pintype "passive"))
      (node (ref "U6") (pin "1") (pinfunction "USBDM_1") (pintype "bidirectional"))
    )
    (net (code "77") (name "Net-(U6-USBDP)") (class "Default")
      (node (ref "R2") (pin "2") (pinfunction "2_2") (pintype "passive"))
      (node (ref "U6") (pin "12") (pinfunction "USBDP_12") (pintype "bidirectional"))
    )
    (net (code "78") (name "Net-(U6-VCC)") (class "Default")
      (node (ref "C7") (pin "1") (pinfunction "1_1") (pintype "bidirectional"))
      (node (ref "FB2") (pin "P$1") (pinfunction "P$1_P$1") (pintype "bidirectional"))
      (node (ref "U6") (pin "4") (pinfunction "VCC_4") (pintype "bidirectional"))
    )
    (net (code "79") (name "Net-(U7-B7)") (class "Default")
      (node (ref "R6") (pin "2") (pinfunction "2_2") (pintype "passive"))
      (node (ref "U7") (pin "13") (pinfunction "B7_13") (pintype "bidirectional"))
    )
    (net (code "80") (name "Net-(U7-B8)") (class "Default")
      (node (ref "R7") (pin "2") (pinfunction "2_2") (pintype "passive"))
      (node (ref "U7") (pin "12") (pinfunction "B8_12") (pintype "bidirectional"))
    )
    (net (code "81") (name "PPS") (class "Default")
      (node (ref "J1") (pin "25") (pinfunction "PPS_25") (pintype "bidirectional"))
      (node (ref "U3") (pin "3") (pinfunction "1PPS_3") (pintype "bidirectional"))
    )
    (net (code "82") (name "SD_DETECT") (class "Default")
      (node (ref "J2") (pin "A") (pinfunction "A_A") (pintype "bidirectional"))
      (node (ref "R22") (pin "1") (pinfunction "1_1") (pintype "passive"))
      (node (ref "U2") (pin "36") (pinfunction "PA17_36") (pintype "bidirectional"))
    )
    (net (code "83") (name "SD_ENABLE") (class "Default")
      (node (ref "Q2") (pin "1") (pinfunction "G_1") (pintype "passive"))
      (node (ref "R13") (pin "2") (pinfunction "2_2") (pintype "passive"))
      (node (ref "U2") (pin "41") (pinfunction "PA21_41") (pintype "bidirectional"))
    )
    (net (code "84") (name "SD_MISO") (class "Default")
      (node (ref "J10") (pin "2") (pinfunction "2_2") (pintype "passive"))
      (node (ref "J2") (pin "7") (pinfunction "DATA0/MISO_7") (pintype "bidirectional"))
      (node (ref "R16") (pin "1") (pinfunction "1_1") (pintype "passive"))
      (node (ref "U2") (pin "34") (pinfunction "PA15_34") (pintype "bidirectional"))
    )
    (net (code "85") (name "SD_MOSI") (class "Default")
      (node (ref "J10") (pin "1") (pinfunction "1_1") (pintype "passive"))
      (node (ref "J2") (pin "3") (pinfunction "CMD/MOSI_3") (pintype "bidirectional"))
      (node (ref "R14") (pin "1") (pinfunction "1_1") (pintype "passive"))
      (node (ref "U2") (pin "35") (pinfunction "PA16_35") (pintype "bidirectional"))
    )
    (net (code "86") (name "SD_SCLK") (class "Default")
      (node (ref "J10") (pin "3") (pinfunction "3_3") (pintype "passive"))
      (node (ref "J2") (pin "5") (pinfunction "CLK_5") (pintype "bidirectional"))
      (node (ref "U2") (pin "33") (pinfunction "PA14_33") (pintype "bidirectional"))
    )
    (net (code "87") (name "SMBCLK") (class "Default")
      (node (ref "J1") (pin "5") (pinfunction "SMBCLK_5") (pintype "bidirectional"))
      (node (ref "U1") (pin "42") (pinfunction "PA22_42") (pintype "bidirectional"))
    )
    (net (code "88") (name "SMBDATA") (class "Default")
      (node (ref "J1") (pin "3") (pinfunction "SMBDATA_3") (pintype "bidirectional"))
      (node (ref "U1") (pin "41") (pinfunction "PA21_41") (pintype "bidirectional"))
    )
    (net (code "89") (name "STORAGE_SWDCLK") (class "Default")
      (node (ref "J6") (pin "4") (pinfunction "SWDCLK_4") (pintype "bidirectional"))
      (node (ref "R19") (pin "1") (pinfunction "1_1") (pintype "passive"))
      (node (ref "U2") (pin "9") (pinfunction "TCK_9") (pintype "bidirectional"))
    )
    (net (code "90") (name "STORAGE_SWDIO") (class "Default")
      (node (ref "J6") (pin "2") (pinfunction "SWDIO_2") (pintype "bidirectional"))
      (node (ref "R18") (pin "1") (pinfunction "1_1") (pintype "passive"))
      (node (ref "U2") (pin "10") (pinfunction "PA03_10") (pintype "bidirectional"))
    )
    (net (code "91") (name "STORAGE_XIN") (class "Default")
      (node (ref "C1") (pin "1") (pinfunction "1_1") (pintype "bidirectional"))
      (node (ref "U2") (pin "1") (pinfunction "PA00_1") (pintype "bidirectional"))
      (node (ref "X1") (pin "3") (pinfunction "2_3") (pintype "bidirectional"))
    )
    (net (code "92") (name "STORAGE_XOUT") (class "Default")
      (node (ref "C2") (pin "1") (pinfunction "1_1") (pintype "bidirectional"))
      (node (ref "U2") (pin "2") (pinfunction "PA01_2") (pintype "bidirectional"))
      (node (ref "X1") (pin "1") (pinfunction "1_1") (pintype "bidirectional"))
    )
    (net (code "93") (name "USB_ATTACHED_3V3") (class "Default")
      (node (ref "J8") (pin "2") (pinfunction "2_2") (pintype "passive"))
      (node (ref "Q1") (pin "1") (pinfunction "G_1") (pintype "passive"))
      (node (ref "U5") (pin "10") (pinfunction "S_10") (pintype "bidirectional"))
    )
    (net (code "94") (name "USB_MOD_D+") (class "Default")
      (node (ref "J1") (pin "27") (pinfunction "USB_D+_27") (pintype "bidirectional"))
      (node (ref "U5") (pin "1") (pinfunction "D1+_1") (pintype "bidirectional"))
    )
    (net (code "95") (name "USB_MOD_D-") (class "Default")
      (node (ref "J1") (pin "28") (pinfunction "USB_D-_28") (pintype "bidirectional"))
      (node (ref "U5") (pin "7") (pinfunction "D1-_7") (pintype "bidirectional"))
    )
    (net (code "96") (name "USB_VBUS") (class "Default")
      (node (ref "D1") (pin "ANODE") (pinfunction "ANODE_ANODE") (pintype "bidirectional"))
      (node (ref "E_1") (pin "20") (pinfunction "USB_VBUS_20") (pintype "bidirectional"))
      (node (ref "J4") (pin "1") (pinfunction "+5V_1") (pintype "bidirectional"))
      (node (ref "R23") (pin "2") (pinfunction "2_2") (pintype "passive"))
    )
    (net (code "97") (name "VCC_CONTROLLER") (class "Default")
      (node (ref "C10") (pin "1") (pinfunction "1_1") (pintype "bidirectional"))
      (node (ref "C11") (pin "1") (pinfunction "1_1") (pintype "bidirectional"))
      (node (ref "C14") (pin "1") (pinfunction "1_1") (pintype "bidirectional"))
      (node (ref "C15") (pin "1") (pinfunction "1_1") (pintype "bidirectional"))
      (node (ref "C16") (pin "1") (pinfunction "1_1") (pintype "bidirectional"))
      (node (ref "C18") (pin "1") (pinfunction "1_1") (pintype "bidirectional"))
      (node (ref "C19") (pin "1") (pinfunction "1_1") (pintype "bidirectional"))
      (node (ref "C29") (pin "1") (pinfunction "1_1") (pintype "bidirectional"))
      (node (ref "C9") (pin "1") (pinfunction "1_1") (pintype "bidirectional"))
      (node (ref "D2") (pin "1") (pinfunction "VDD_1") (pintype "bidirectional"))
      (node (ref "FB3") (pin "2") (pinfunction "P$2_2") (pintype "bidirectional"))
      (node (ref "FB4") (pin "2") (pinfunction "P$2_2") (pintype "bidirectional"))
      (node (ref "J1") (pin "2") (pinfunction "VCC_CONTROLLER_2") (pintype "bidirectional"))
      (node (ref "J10") (pin "20") (pinfunction "20_20") (pintype "passive"))
      (node (ref "J6") (pin "1") (pinfunction "VCC_1") (pintype "bidirectional"))
      (node (ref "J7") (pin "1") (pinfunction "VCC_1") (pintype "bidirectional"))
      (node (ref "Q2") (pin "2") (pinfunction "S_2") (pintype "passive"))
      (node (ref "R11") (pin "2") (pinfunction "2_2") (pintype "passive"))
      (node (ref "R12") (pin "2") (pinfunction "2_2") (pintype "passive"))
      (node (ref "R18") (pin "2") (pinfunction "2_2") (pintype "passive"))
      (node (ref "R19") (pin "2") (pinfunction "2_2") (pintype "passive"))
      (node (ref "R20") (pin "2") (pinfunction "2_2") (pintype "passive"))
      (node (ref "R21") (pin "2") (pinfunction "2_2") (pintype "passive"))
      (node (ref "U1") (pin "27") (pinfunction "VLCD_27") (pintype "bidirectional"))
      (node (ref "U1") (pin "31") (pinfunction "VLCDIN_31") (pintype "power_in"))
      (node (ref "U1") (pin "40") (pinfunction "VDDIO_40") (pintype "power_in"))
      (node (ref "U1") (pin "45") (pinfunction "VDDIO_45") (pintype "power_in"))
      (node (ref "U1") (pin "8") (pinfunction "VDDIN_8") (pintype "power_in"))
      (node (ref "U2") (pin "27") (pinfunction "VLCD_27") (pintype "bidirectional"))
      (node (ref "U2") (pin "31") (pinfunction "VLCDIN_31") (pintype "power_in"))
      (node (ref "U2") (pin "40") (pinfunction "VDDIO_40") (pintype "power_in"))
      (node (ref "U2") (pin "45") (pinfunction "VDDIO_45") (pintype "power_in"))
      (node (ref "U2") (pin "8") (pinfunction "VDDIN_8") (pintype "power_in"))
      (node (ref "U3") (pin "11") (pinfunction "VBACKUP_11") (pintype "bidirectional"))
      (node (ref "U3") (pin "12") (pinfunction "VCC_12") (pintype "bidirectional"))
      (node (ref "U4") (pin "3") (pinfunction "~{WP}_3") (pintype "bidirectional"))
      (node (ref "U4") (pin "7") (pinfunction "~{HOLD}_7") (pintype "bidirectional"))
      (node (ref "U4") (pin "8") (pinfunction "VDD_8") (pintype "bidirectional"))
    )
    (net (code "98") (name "VCC_LINUX") (class "Default")
      (node (ref "J1") (pin "4") (pinfunction "VCC_LINUX_4") (pintype "bidirectional"))
      (node (ref "J10") (pin "17") (pinfunction "17_17") (pintype "passive"))
      (node (ref "J14") (pin "1") (pinfunction "1_1") (pintype "passive"))
      (node (ref "J15") (pin "1") (pinfunction "1_1") (pintype "passive"))
    )
    (net (code "99") (name "VCC_LINUX_1V8") (class "Default")
      (node (ref "C23") (pin "1") (pinfunction "1_1") (pintype "bidirectional"))
      (node (ref "C24") (pin "2") (pinfunction "2_2") (pintype "bidirectional"))
      (node (ref "E_1") (pin "12") (pinfunction "1.8V_12") (pintype "bidirectional"))
      (node (ref "J10") (pin "14") (pinfunction "14_14") (pintype "passive"))
      (node (ref "U6") (pin "9") (pinfunction "VCCIO_9") (pintype "bidirectional"))
      (node (ref "U7") (pin "10") (pinfunction "OE_10") (pintype "bidirectional"))
      (node (ref "U7") (pin "2") (pinfunction "VCCA_2") (pintype "bidirectional"))
    )
    (net (code "100") (name "VCC_LINUX_3V3") (class "Default")
      (node (ref "C20") (pin "1") (pinfunction "1_1") (pintype "bidirectional"))
      (node (ref "C21") (pin "2") (pinfunction "2_2") (pintype "bidirectional"))
      (node (ref "C22") (pin "1") (pinfunction "1_1") (pintype "bidirectional"))
      (node (ref "C30") (pin "P$1") (pinfunction "1_P$1") (pintype "bidirectional"))
      (node (ref "D3") (pin "1") (pinfunction "VDD_1") (pintype "bidirectional"))
      (node (ref "E_1") (pin "14") (pinfunction "DCIN_14") (pintype "bidirectional"))
      (node (ref "E_1") (pin "2") (pinfunction "VSYS_2") (pintype "bidirectional"))
      (node (ref "E_1") (pin "4") (pinfunction "VSYS_4") (pintype "bidirectional"))
      (node (ref "E_1") (pin "6") (pinfunction "VSYS_6") (pintype "bidirectional"))
      (node (ref "J10") (pin "18") (pinfunction "18_18") (pintype "passive"))
      (node (ref "J8") (pin "3") (pinfunction "3_3") (pintype "passive"))
      (node (ref "L1") (pin "P$2") (pinfunction "2_P$2") (pintype "bidirectional"))
      (node (ref "R17") (pin "2") (pinfunction "2_2") (pintype "passive"))
      (node (ref "U5") (pin "9") (pinfunction "VCC_9") (pintype "bidirectional"))
      (node (ref "U7") (pin "19") (pinfunction "VCCB_19") (pintype "bidirectional"))
      (node (ref "VR1") (pin "3") (pinfunction "FB_3") (pintype "bidirectional"))
      (node (ref "VR1") (pin "4") (pinfunction "VOS_4") (pintype "bidirectional"))
    )
    (net (code "101") (name "unconnected-(E_1A-3.3V-Pad8)") (class "Default")
      (node (ref "E_1") (pin "8") (pinfunction "3.3V_8") (pintype "bidirectional"))
    )
    (net (code "102") (name "unconnected-(E_1A-3.3V-Pad10)") (class "Default")
      (node (ref "E_1") (pin "10") (pinfunction "3.3V_10") (pintype "bidirectional"))
    )
    (net (code "103") (name "unconnected-(E_1A-FW_RCVR-Pad69)") (class "Default")
      (node (ref "E_1") (pin "69") (pinfunction "FW_RCVR_69") (pintype "bidirectional"))
    )
    (net (code "104") (name "unconnected-(E_1A-MSIC_SLP_CLK-Pad7)") (class "Default")
      (node (ref "E_1") (pin "7") (pinfunction "MSIC_SLP_CLK_7") (pintype "bidirectional"))
    )
    (net (code "105") (name "unconnected-(E_1A-OSC_CLK_OUT_0-Pad67)") (class "Default")
      (node (ref "E_1") (pin "67") (pinfunction "OSC_CLK_OUT_0_67") (pintype "bidirectional"))
    )
    (net (code "106") (name "unconnected-(E_1A-RCVR_MODE-Pad31)") (class "Default")
      (node (ref "E_1") (pin "31") (pinfunction "RCVR_MODE_31") (pintype "bidirectional"))
    )
    (net (code "107") (name "unconnected-(E_1A-RESET_OUT#-Pad36)") (class "Default")
      (node (ref "E_1") (pin "36") (pinfunction "RESET_OUT#_36") (pintype "bidirectional"))
    )
    (net (code "108") (name "unconnected-(E_1A-V_VAT_BKUP-Pad23)") (class "Default")
      (node (ref "E_1") (pin "23") (pinfunction "V_VAT_BKUP_23") (pintype "bidirectional"))
    )
    (net (code "109") (name "unconnected-(E_1B-GP13_PWM1-Pad33)") (class "Default")
      (node (ref "E_1") (pin "33") (pinfunction "GP13_PWM1_33") (pintype "bidirectional"))
    )
    (net (code "110") (name "unconnected-(E_1B-GP14-Pad48)") (class "Default")
      (node (ref "E_1") (pin "48") (pinfunction "GP14_48") (pintype "bidirectional"))
    )
    (net (code "111") (name "unconnected-(E_1B-GP15-Pad42)") (class "Default")
      (node (ref "E_1") (pin "42") (pinfunction "GP15_42") (pintype "bidirectional"))
    )
    (net (code "112") (name "unconnected-(E_1B-GP44-Pad24)") (class "Default")
      (node (ref "E_1") (pin "24") (pinfunction "GP44_24") (pintype "bidirectional"))
    )
    (net (code "113") (name "unconnected-(E_1B-GP45-Pad26)") (class "Default")
      (node (ref "E_1") (pin "26") (pinfunction "GP45_26") (pintype "bidirectional"))
    )
    (net (code "114") (name "unconnected-(E_1B-GP46-Pad28)") (class "Default")
      (node (ref "E_1") (pin "28") (pinfunction "GP46_28") (pintype "bidirectional"))
    )
    (net (code "115") (name "unconnected-(E_1B-GP47-Pad30)") (class "Default")
      (node (ref "E_1") (pin "30") (pinfunction "GP47_30") (pintype "bidirectional"))
    )
    (net (code "116") (name "unconnected-(E_1B-GP48-Pad32)") (class "Default")
      (node (ref "E_1") (pin "32") (pinfunction "GP48_32") (pintype "bidirectional"))
    )
    (net (code "117") (name "unconnected-(E_1B-GP49-Pad34)") (class "Default")
      (node (ref "E_1") (pin "34") (pinfunction "GP49_34") (pintype "bidirectional"))
    )
    (net (code "118") (name "unconnected-(E_1B-GP165-Pad25)") (class "Default")
      (node (ref "E_1") (pin "25") (pinfunction "GP165_25") (pintype "bidirectional"))
    )
    (net (code "119") (name "unconnected-(E_1B-GP183_PWM3-Pad39)") (class "Default")
      (node (ref "E_1") (pin "39") (pinfunction "GP183_PWM3_39") (pintype "bidirectional"))
    )
    (net (code "120") (name "unconnected-(E_1C-GP19_I2C_1_SCL-Pad41)") (class "Default")
      (node (ref "E_1") (pin "41") (pinfunction "GP19_I2C_1_SCL_41") (pintype "bidirectional"))
    )
    (net (code "121") (name "unconnected-(E_1C-GP20_I2C_1_SDA-Pad43)") (class "Default")
      (node (ref "E_1") (pin "43") (pinfunction "GP20_I2C_1_SDA_43") (pintype "bidirectional"))
    )
    (net (code "122") (name "unconnected-(E_1E-GP40_I2S_2_CLK-Pad52)") (class "Default")
      (node (ref "E_1") (pin "52") (pinfunction "GP40_I2S_2_CLK_52") (pintype "bidirectional"))
    )
    (net (code "123") (name "unconnected-(E_1E-GP41_I2S_2_FS-Pad54)") (class "Default")
      (node (ref "E_1") (pin "54") (pinfunction "GP41_I2S_2_FS_54") (pintype "bidirectional"))
    )
    (net (code "124") (name "unconnected-(E_1E-GP42_I2S_2_RXD-Pad50)") (class "Default")
      (node (ref "E_1") (pin "50") (pinfunction "GP42_I2S_2_RXD_50") (pintype "bidirectional"))
    )
    (net (code "125") (name "unconnected-(E_1E-GP43_I2S_2_TXD-Pad56)") (class "Default")
      (node (ref "E_1") (pin "56") (pinfunction "GP43_I2S_2_TXD_56") (pintype "bidirectional"))
    )
    (net (code "126") (name "unconnected-(E_1F-GP77_SD_0_CD#-Pad60)") (class "Default")
      (node (ref "E_1") (pin "60") (pinfunction "GP77_SD_0_CD#_60") (pintype "bidirectional"))
    )
    (net (code "127") (name "unconnected-(E_1F-GP78_SD_0_CLK-Pad58)") (class "Default")
      (node (ref "E_1") (pin "58") (pinfunction "GP78_SD_0_CLK_58") (pintype "bidirectional"))
    )
    (net (code "128") (name "unconnected-(E_1F-GP79_SD_0_CMD-Pad62)") (class "Default")
      (node (ref "E_1") (pin "62") (pinfunction "GP79_SD_0_CMD_62") (pintype "bidirectional"))
    )
    (net (code "129") (name "unconnected-(E_1F-GP80_SD_0_DAT0-Pad66)") (class "Default")
      (node (ref "E_1") (pin "66") (pinfunction "GP80_SD_0_DAT0_66") (pintype "bidirectional"))
    )
    (net (code "130") (name "unconnected-(E_1F-GP81_SD_0_DAT1-Pad70)") (class "Default")
      (node (ref "E_1") (pin "70") (pinfunction "GP81_SD_0_DAT1_70") (pintype "bidirectional"))
    )
    (net (code "131") (name "unconnected-(E_1F-GP82_SD_0_DAT2-Pad64)") (class "Default")
      (node (ref "E_1") (pin "64") (pinfunction "GP82_SD_0_DAT2_64") (pintype "bidirectional"))
    )
    (net (code "132") (name "unconnected-(E_1F-GP83_SD_0_DAT3-Pad68)") (class "Default")
      (node (ref "E_1") (pin "68") (pinfunction "GP83_SD_0_DAT3_68") (pintype "bidirectional"))
    )
    (net (code "133") (name "unconnected-(E_1F-GP84_SD_0_CLK_FB-Pad44)") (class "Default")
      (node (ref "E_1") (pin "44") (pinfunction "GP84_SD_0_CLK_FB_44") (pintype "bidirectional"))
    )
    (net (code "134") (name "unconnected-(E_1H-GP128_UART_1_CTS-Pad65)") (class "Default")
      (node (ref "E_1") (pin "65") (pinfunction "GP128_UART_1_CTS_65") (pintype "bidirectional"))
    )
    (net (code "135") (name "unconnected-(E_1H-GP129_UART_1_RTS-Pad63)") (class "Default")
      (node (ref "E_1") (pin "63") (pinfunction "GP129_UART_1_RTS_63") (pintype "bidirectional"))
    )
    (net (code "136") (name "unconnected-(E_1H-GP130_UART_1_RX-Pad61)") (class "Default")
      (node (ref "E_1") (pin "61") (pinfunction "GP130_UART_1_RX_61") (pintype "bidirectional"))
    )
    (net (code "137") (name "unconnected-(E_1H-GP131_UART_1_TX-Pad46)") (class "Default")
      (node (ref "E_1") (pin "46") (pinfunction "GP131_UART_1_TX_46") (pintype "bidirectional"))
    )
    (net (code "138") (name "unconnected-(E_1J-FAULT-Pad19)") (class "Default")
      (node (ref "E_1") (pin "19") (pinfunction "FAULT_19") (pintype "bidirectional"))
    )
    (net (code "139") (name "unconnected-(E_1J-PSW-Pad21)") (class "Default")
      (node (ref "E_1") (pin "21") (pinfunction "PSW_21") (pintype "bidirectional"))
    )
    (net (code "140") (name "unconnected-(J2-DATA1{slash}RSV-Pad8)") (class "Default")
      (node (ref "J2") (pin "8") (pinfunction "DATA1/RSV_8") (pintype "bidirectional"))
    )
    (net (code "141") (name "unconnected-(J2-DATA2{slash}NC-Pad1)") (class "Default")
      (node (ref "J2") (pin "1") (pinfunction "DATA2/NC_1") (pintype "bidirectional"))
    )
    (net (code "142") (name "unconnected-(J4-ID-Pad4)") (class "Default")
      (node (ref "J4") (pin "4") (pinfunction "ID_4") (pintype "bidirectional"))
    )
    (net (code "143") (name "unconnected-(J5-ID-Pad4)") (class "Default")
      (node (ref "J5") (pin "4") (pinfunction "ID_4") (pintype "bidirectional"))
    )
    (net (code "144") (name "unconnected-(J6-SWO-Pad6)") (class "Default")
      (node (ref "J6") (pin "6") (pinfunction "SWO_6") (pintype "bidirectional"))
    )
    (net (code "145") (name "unconnected-(J7-SWO-Pad6)") (class "Default")
      (node (ref "J7") (pin "6") (pinfunction "SWO_6") (pintype "bidirectional"))
    )
    (net (code "146") (name "unconnected-(U1-ADVREFP-Pad18)") (class "Default")
      (node (ref "U1") (pin "18") (pinfunction "ADVREFP_18") (pintype "bidirectional"))
    )
    (net (code "147") (name "unconnected-(U1-XIN32-Pad13)") (class "Default")
      (node (ref "U1") (pin "13") (pinfunction "XIN32_13") (pintype "bidirectional"))
    )
    (net (code "148") (name "unconnected-(U1-XOUT32-Pad14)") (class "Default")
      (node (ref "U1") (pin "14") (pinfunction "XOUT32_14") (pintype "bidirectional"))
    )
    (net (code "149") (name "unconnected-(U2-ADVREFP-Pad18)") (class "Default")
      (node (ref "U2") (pin "18") (pinfunction "ADVREFP_18") (pintype "bidirectional"))
    )
    (net (code "150") (name "unconnected-(U2-PA04-Pad11)") (class "Default")
      (node (ref "U2") (pin "11") (pinfunction "PA04_11") (pintype "bidirectional"))
    )
    (net (code "151") (name "unconnected-(U2-PA08-Pad20)") (class "Default")
      (node (ref "U2") (pin "20") (pinfunction "PA08_20") (pintype "bidirectional"))
    )
    (net (code "152") (name "unconnected-(U2-PA25-Pad46)") (class "Default")
      (node (ref "U2") (pin "46") (pinfunction "PA25_46") (pintype "bidirectional"))
    )
    (net (code "153") (name "unconnected-(U2-PA26-Pad47)") (class "Default")
      (node (ref "U2") (pin "47") (pinfunction "PA26_47") (pintype "bidirectional"))
    )
    (net (code "154") (name "unconnected-(U2-XIN32-Pad13)") (class "Default")
      (node (ref "U2") (pin "13") (pinfunction "XIN32_13") (pintype "bidirectional"))
    )
    (net (code "155") (name "unconnected-(U2-XOUT32-Pad14)") (class "Default")
      (node (ref "U2") (pin "14") (pinfunction "XOUT32_14") (pintype "bidirectional"))
    )
    (net (code "156") (name "unconnected-(U3-~{RESET}-Pad8)") (class "Default")
      (node (ref "U3") (pin "8") (pinfunction "~{RESET}_8") (pintype "bidirectional"))
    )
    (net (code "157") (name "unconnected-(U6-3V3OUT-Pad3)") (class "Default")
      (node (ref "U6") (pin "3") (pinfunction "3V3OUT_3") (pintype "bidirectional"))
    )
    (net (code "158") (name "unconnected-(U6-CBUS0-Pad6)") (class "Default")
      (node (ref "U6") (pin "6") (pinfunction "CBUS0_6") (pintype "bidirectional"))
    )
    (net (code "159") (name "unconnected-(U6-~{CTS}-Pad11)") (class "Default")
      (node (ref "U6") (pin "11") (pinfunction "~{CTS}_11") (pintype "bidirectional"))
    )
    (net (code "160") (name "unconnected-(U6-~{RESET}-Pad2)") (class "Default")
      (node (ref "U6") (pin "2") (pinfunction "~{RESET}_2") (pintype "bidirectional"))
    )
    (net (code "161") (name "unconnected-(U6-~{RTS}-Pad8)") (class "Default")
      (node (ref "U6") (pin "8") (pinfunction "~{RTS}_8") (pintype "bidirectional"))
    )
    (net (code "162") (name "unconnected-(VR1-PG-Pad2)") (class "Default")
      (node (ref "VR1") (pin "2") (pinfunction "PG_2") (pintype "bidirectional"))
    )
    (net (code "163") (name "~{BACKPLANE_RESET}") (class "Default")
      (node (ref "J1") (pin "22") (pinfunction "~{BACKPLANE_RESET}_22") (pintype "bidirectional"))
      (node (ref "SW1") (pin "1") (pinfunction "P$1_1") (pintype "passive"))
      (node (ref "SW1") (pin "2") (pinfunction "P$1_2") (pintype "passive"))
    )
    (net (code "164") (name "~{CONTROLLER_RESET}") (class "Default")
      (node (ref "J7") (pin "3") (pinfunction "~{RESET}_3") (pintype "bidirectional"))
      (node (ref "U1") (pin "4") (pinfunction "~{RESET}_4") (pintype "bidirectional"))
    )
    (net (code "165") (name "~{EDISON_PWRBTN}") (class "Default")
      (node (ref "E_1") (pin "17") (pinfunction "PWRBTN#_17") (pintype "bidirectional"))
      (node (ref "R17") (pin "1") (pinfunction "1_1") (pintype "passive"))
      (node (ref "U2") (pin "12") (pinfunction "PA05_12") (pintype "bidirectional"))
    )
    (net (code "166") (name "~{EDISON_SPI_CS_1V8}") (class "Default")
      (node (ref "J10") (pin "13") (pinfunction "13_13") (pintype "passive"))
      (node (ref "J13") (pin "2") (pinfunction "2_2") (pintype "passive"))
      (node (ref "U7") (pin "5") (pinfunction "A4_5") (pintype "bidirectional"))
    )
    (net (code "167") (name "~{EDISON_SPI_CS}") (class "Default")
      (node (ref "U2") (pin "42") (pinfunction "PA22_42") (pintype "bidirectional"))
      (node (ref "U7") (pin "16") (pinfunction "B4_16") (pintype "bidirectional"))
    )
    (net (code "168") (name "~{FRAM_CS{slash}CONTROLLER_LED}") (class "Default")
      (node (ref "J10") (pin "9") (pinfunction "9_9") (pintype "passive"))
      (node (ref "R10") (pin "2") (pinfunction "2_2") (pintype "passive"))
      (node (ref "U1") (pin "46") (pinfunction "PA25_46") (pintype "bidirectional"))
      (node (ref "U4") (pin "1") (pinfunction "~{CS}_1") (pintype "bidirectional"))
    )
    (net (code "169") (name "~{SD_CS}") (class "Default")
      (node (ref "J10") (pin "4") (pinfunction "4_4") (pintype "passive"))
      (node (ref "J2") (pin "2") (pinfunction "DATA3-CD/CS_N_2") (pintype "bidirectional"))
      (node (ref "R15") (pin "1") (pinfunction "1_1") (pintype "passive"))
      (node (ref "U2") (pin "32") (pinfunction "PA13_32") (pintype "bidirectional"))
    )
    (net (code "170") (name "~{SMBALERT}") (class "Default")
      (node (ref "J1") (pin "6") (pinfunction "~{SMBALERT}_6") (pintype "bidirectional"))
      (node (ref "U1") (pin "47") (pinfunction "PA26_47") (pintype "bidirectional"))
    )
    (net (code "171") (name "~{STORAGE_CS}") (class "Default")
      (node (ref "J10") (pin "8") (pinfunction "8_8") (pintype "passive"))
      (node (ref "J9") (pin "2") (pinfunction "2_2") (pintype "passive"))
      (node (ref "U2") (pin "21") (pinfunction "PA09_21") (pintype "bidirectional"))
    )
    (net (code "172") (name "~{STORAGE_LED}") (class "Default")
      (node (ref "R9") (pin "2") (pinfunction "2_2") (pintype "passive"))
      (node (ref "U2") (pin "16") (pinfunction "PA07_16") (pintype "bidirectional"))
    )
    (net (code "173") (name "~{STORAGE_RESET}") (class "Default")
      (node (ref "J6") (pin "3") (pinfunction "~{RESET}_3") (pintype "bidirectional"))
      (node (ref "U2") (pin "4") (pinfunction "~{RESET}_4") (pintype "bidirectional"))
    )
  )
)
